# sensor.net
KiCad netlist of a schematic drawn in EAGLE
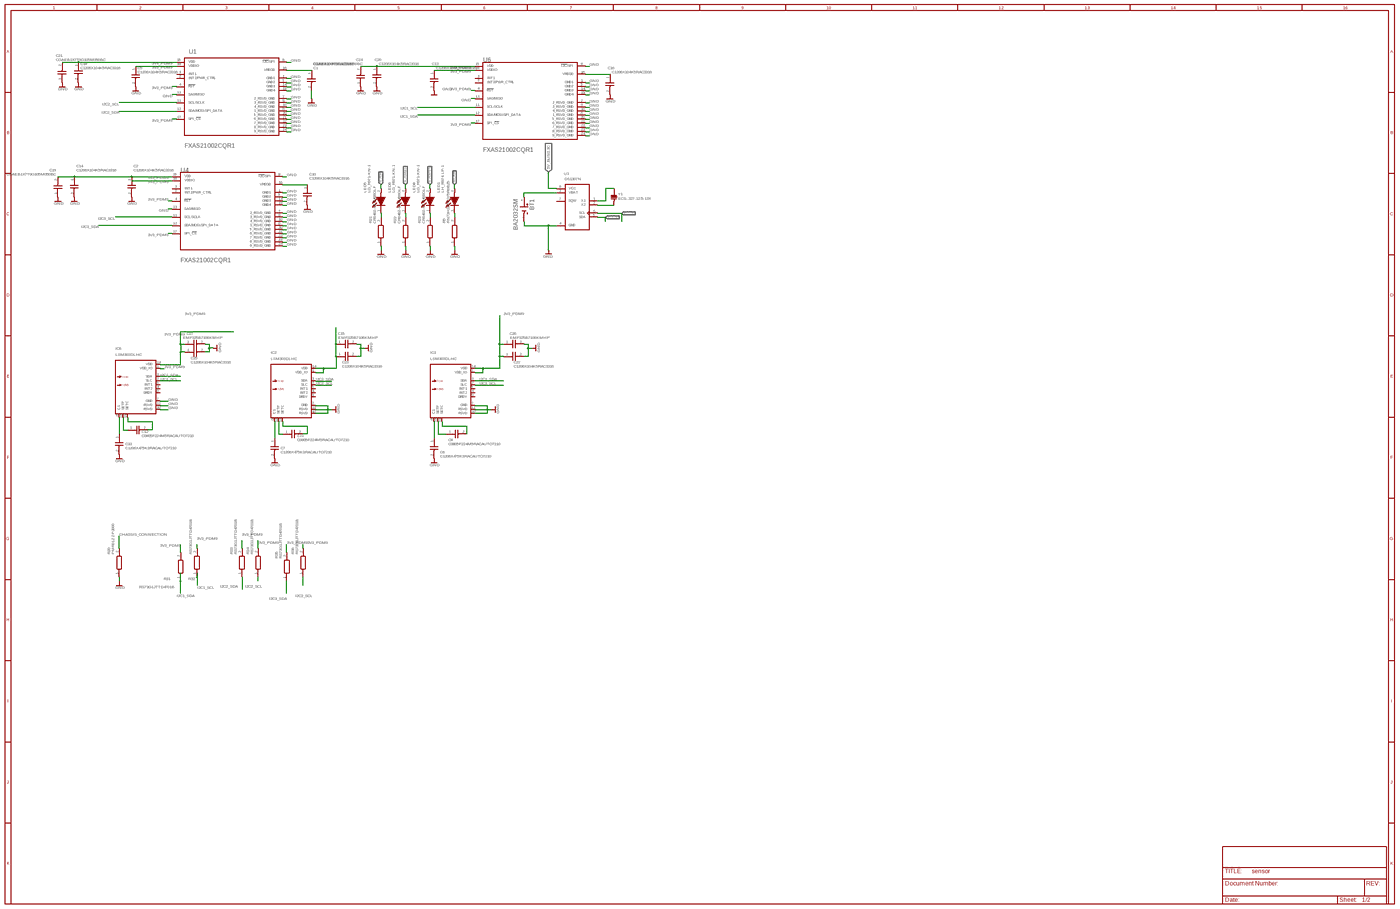
[diagram p0: schematic, sheet 1, overview]
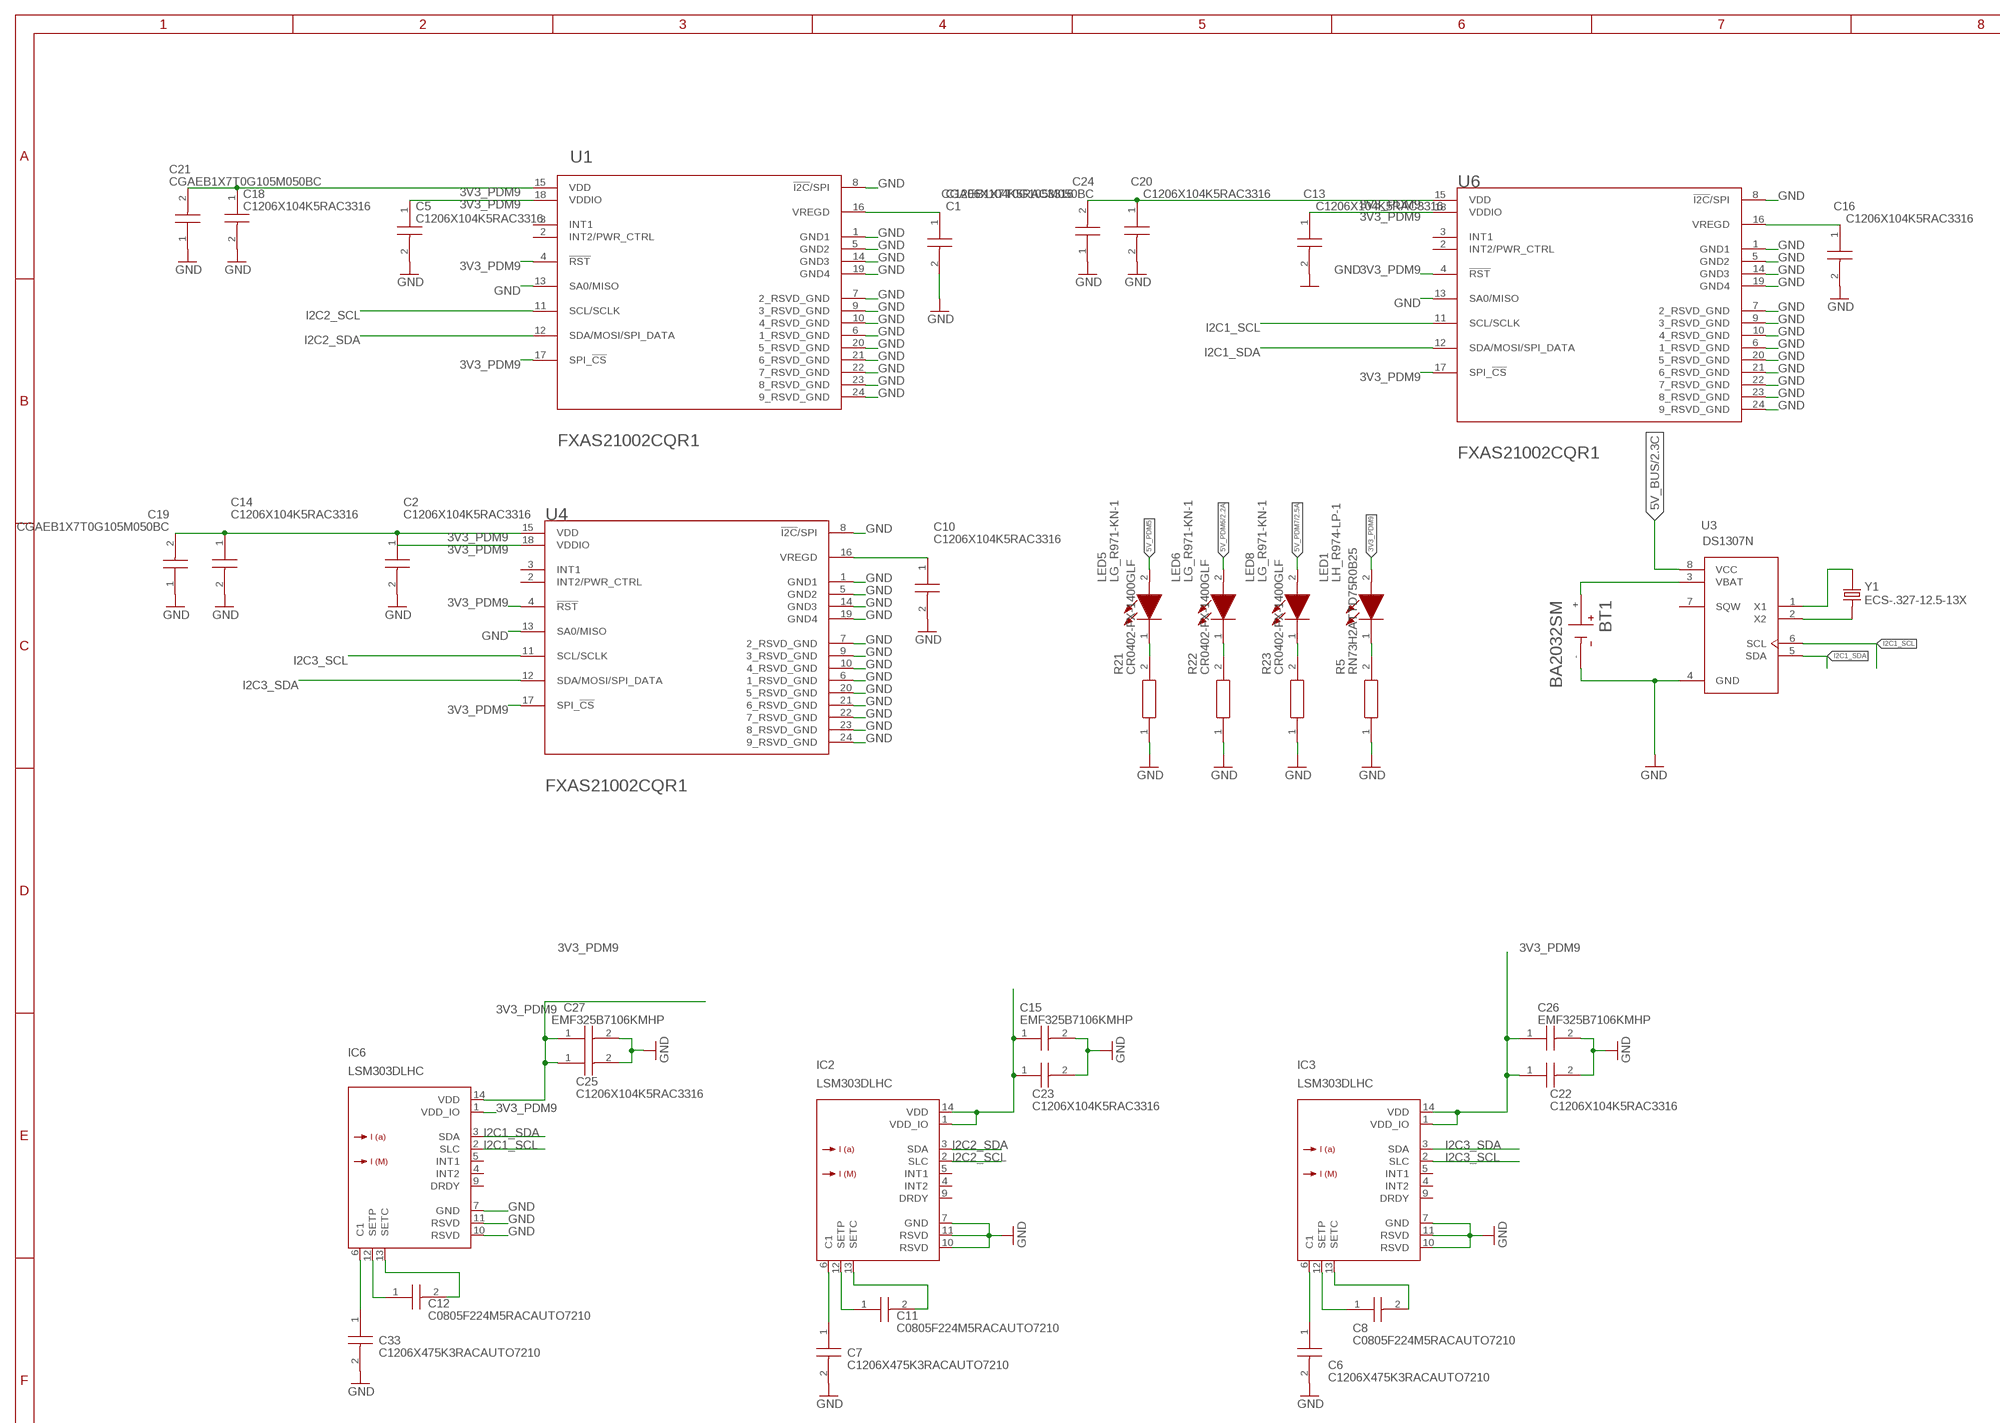
[diagram p1: schematic, sheet 1, part 1 of 4]
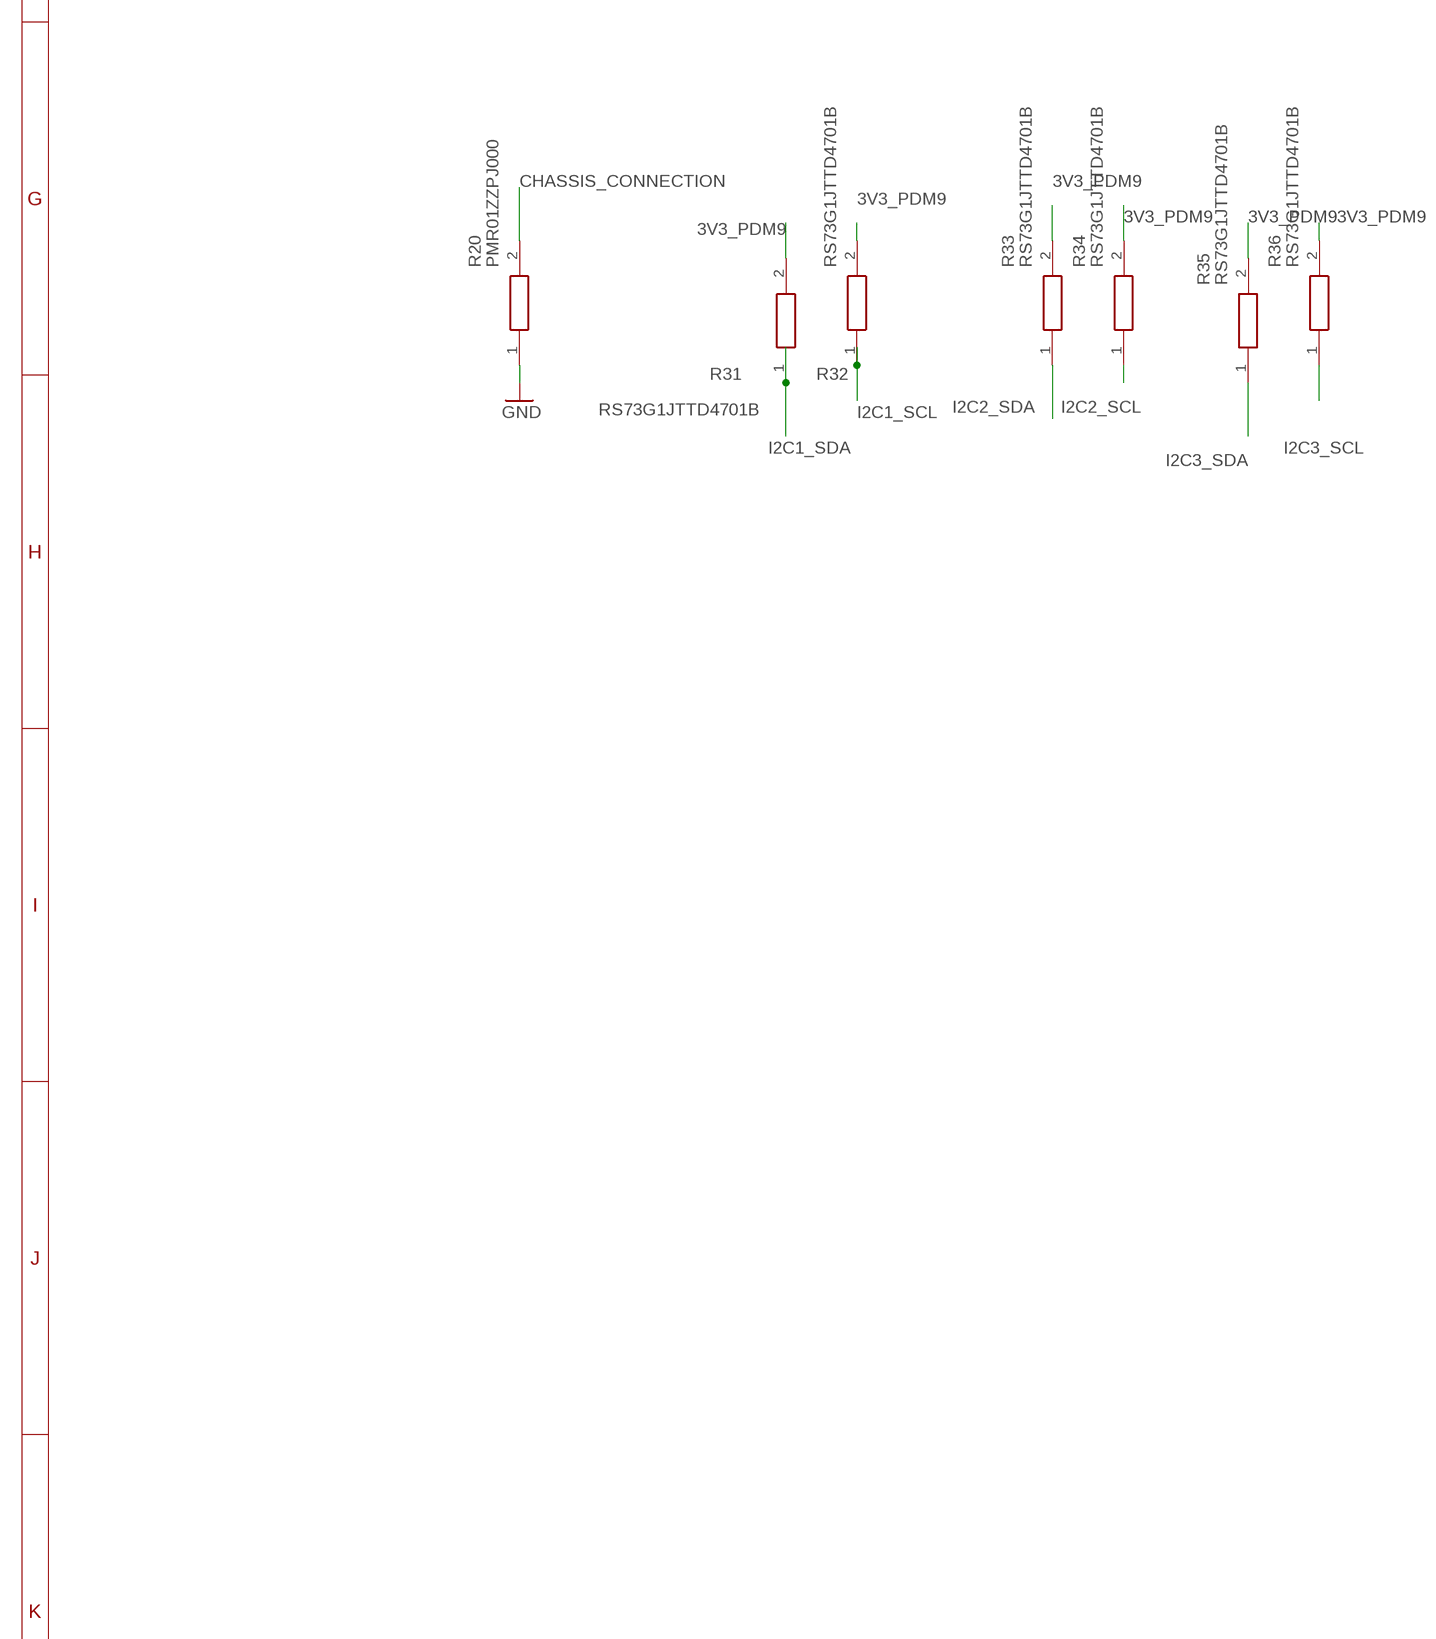
[diagram p2: schematic, sheet 1, part 2 of 4]
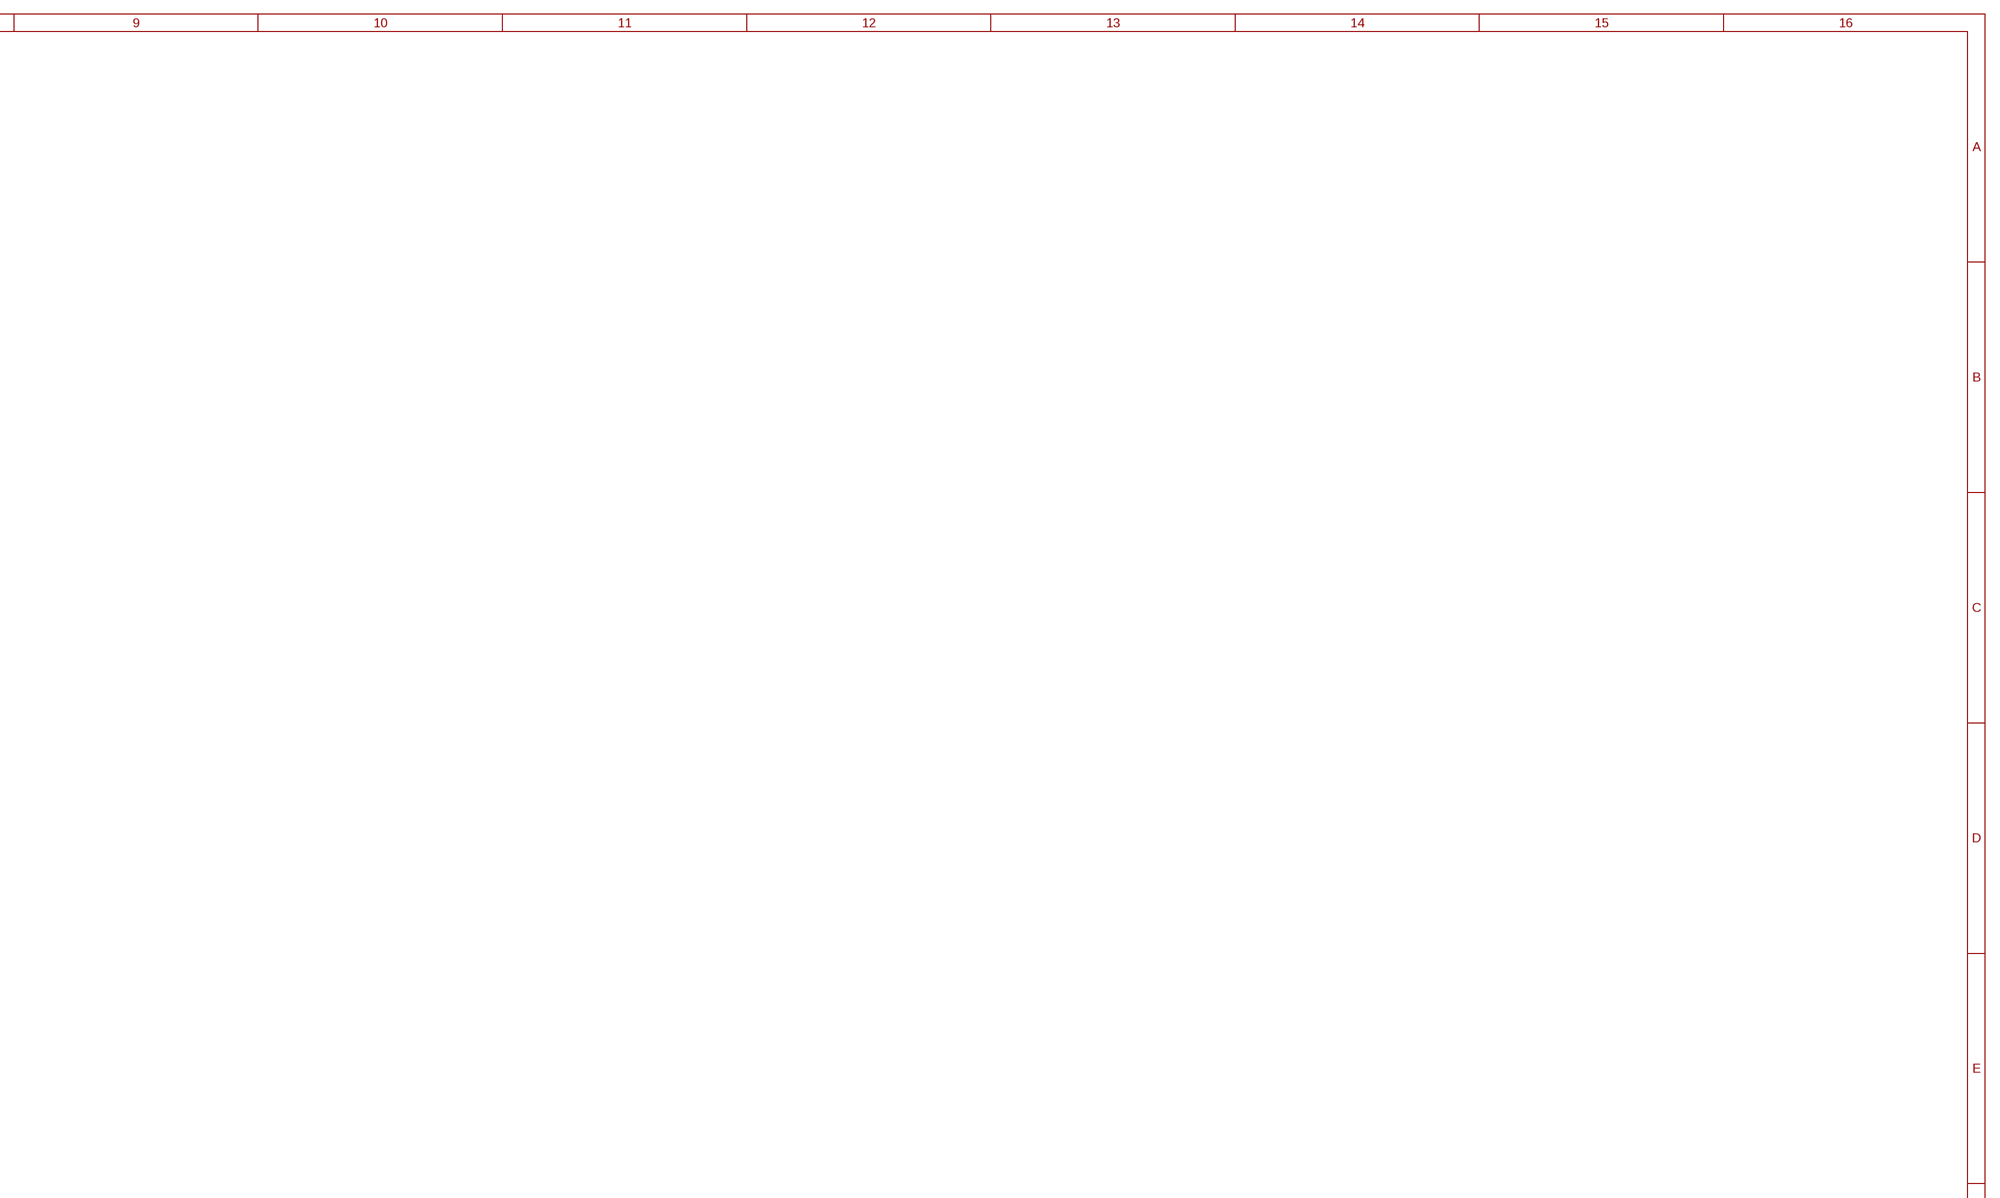
[diagram p3: schematic, sheet 1, part 3 of 4]
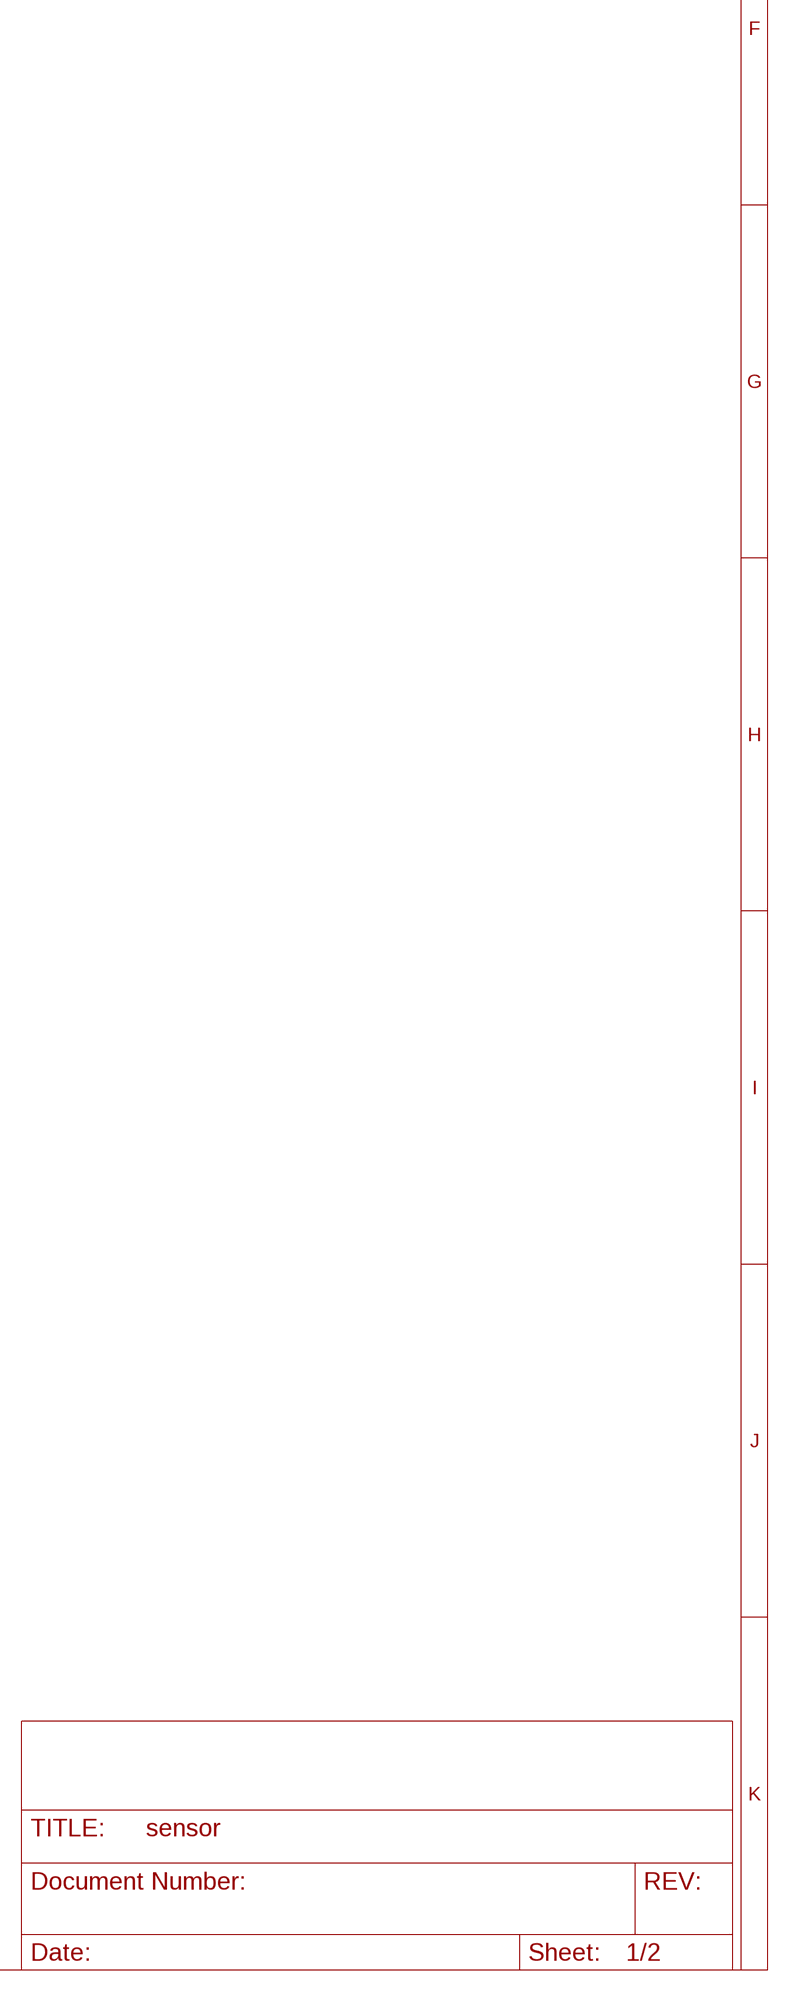
[diagram p4: schematic, sheet 1, part 4 of 4]
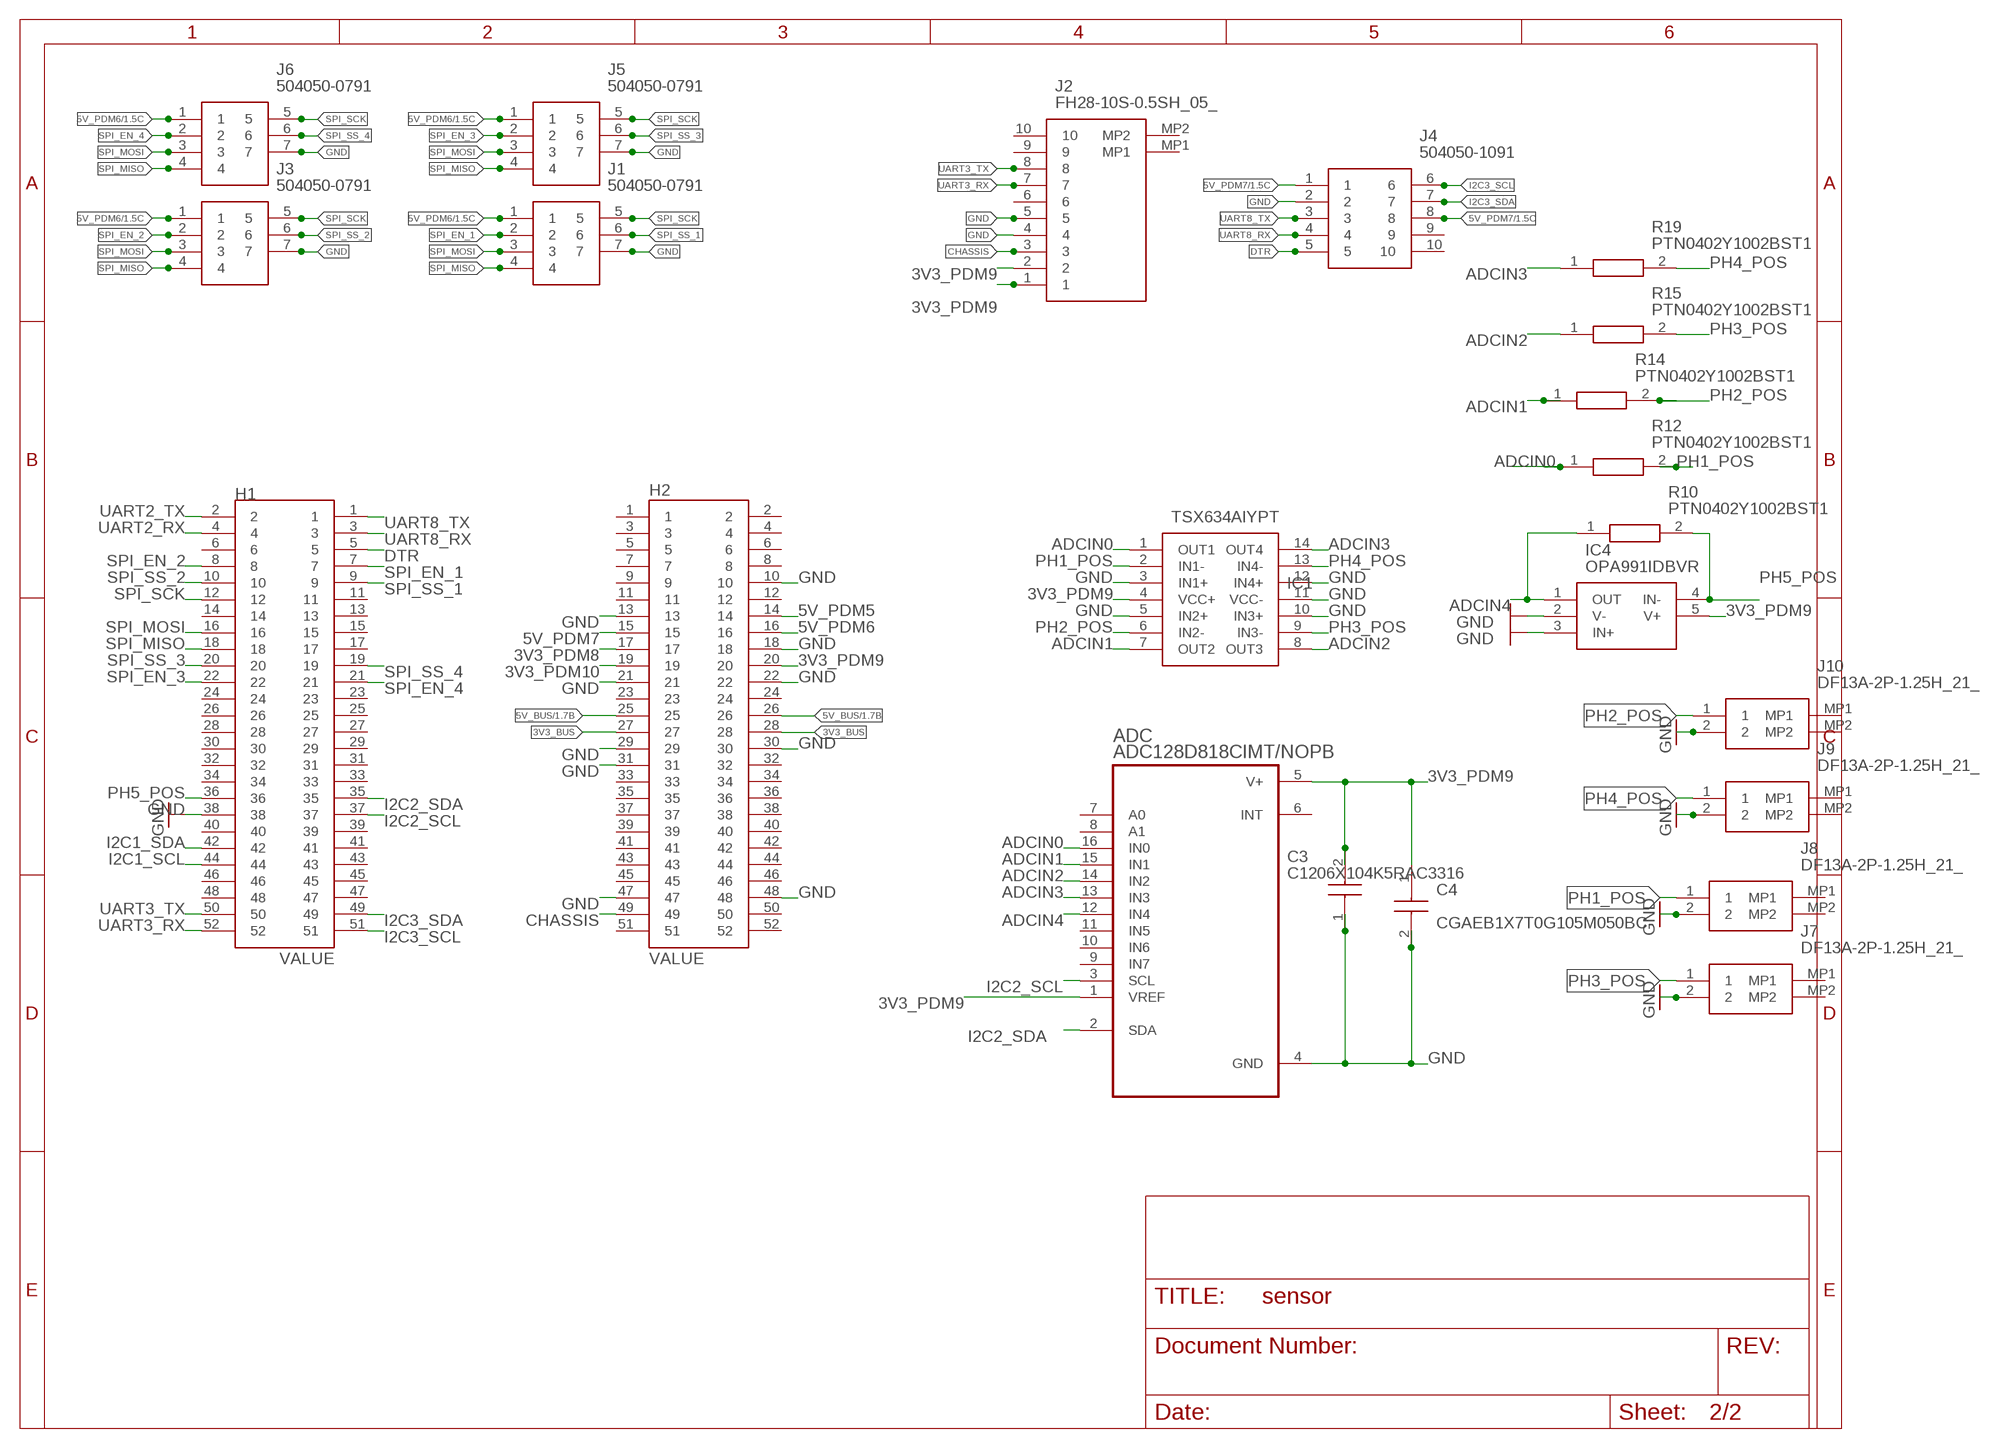
[diagram p5: schematic, sheet 2]

(export (version "E")
  (design (tool "Eeschema 10.0.6"))
  (components
    (comp (ref "BT1")
      (value "BA2032SM")
      (footprint "eagle-import:BAT_BA2032SM")
      (fields (field (name "DIGI-KEY_PART_NUMBER") "BA2032SM-ND") (field (name "MF") "MPD"))
      (libsource (lib "eagle-import") (part "BA2032SM"))
    )
    (comp (ref "C1")
      (value "C1206X104K5RAC3316")
      (footprint "eagle-import:CAPC3316X98N")
      (fields (field (name "MOUSER_PART_NUMBER") "80-C1206X104K5RC3316"))
      (libsource (lib "eagle-import") (part "C1206X104K5RAC3316"))
    )
    (comp (ref "C2")
      (value "C1206X104K5RAC3316")
      (footprint "eagle-import:CAPC3316X98N")
      (fields (field (name "MOUSER_PART_NUMBER") "80-C1206X104K5RC3316"))
      (libsource (lib "eagle-import") (part "C1206X104K5RAC3316"))
    )
    (comp (ref "C5")
      (value "C1206X104K5RAC3316")
      (footprint "eagle-import:CAPC3316X98N")
      (fields (field (name "MOUSER_PART_NUMBER") "80-C1206X104K5RC3316"))
      (libsource (lib "eagle-import") (part "C1206X104K5RAC3316"))
    )
    (comp (ref "C6")
      (value "C1206X475K3RACAUTO7210")
      (footprint "eagle-import:CAPC3316X195N")
      (fields (field (name "MOUSER_PART_NUMBER") "80-C1206X475K3RAUTLR"))
      (libsource (lib "eagle-import") (part "C1206X475K3RACAUTO7210"))
    )
    (comp (ref "C7")
      (value "C1206X475K3RACAUTO7210")
      (footprint "eagle-import:CAPC3316X195N")
      (fields (field (name "MOUSER_PART_NUMBER") "80-C1206X475K3RAUTLR"))
      (libsource (lib "eagle-import") (part "C1206X475K3RACAUTO7210"))
    )
    (comp (ref "C8")
      (value "C0805F224M5RACAUTO7210")
      (footprint "eagle-import:CAPC2012X140N")
      (fields (field (name "MOUSER_PART_NUMBER") "80-C0805F224M5RAUTLR"))
      (libsource (lib "eagle-import") (part "C0805F224M5RACAUTO7210"))
    )
    (comp (ref "C10")
      (value "C1206X104K5RAC3316")
      (footprint "eagle-import:CAPC3316X98N")
      (fields (field (name "MOUSER_PART_NUMBER") "80-C1206X104K5RC3316"))
      (libsource (lib "eagle-import") (part "C1206X104K5RAC3316"))
    )
    (comp (ref "C11")
      (value "C0805F224M5RACAUTO7210")
      (footprint "eagle-import:CAPC2012X140N")
      (fields (field (name "MOUSER_PART_NUMBER") "80-C0805F224M5RAUTLR"))
      (libsource (lib "eagle-import") (part "C0805F224M5RACAUTO7210"))
    )
    (comp (ref "C12")
      (value "C0805F224M5RACAUTO7210")
      (footprint "eagle-import:CAPC2012X140N")
      (fields (field (name "MOUSER_PART_NUMBER") "80-C0805F224M5RAUTLR"))
      (libsource (lib "eagle-import") (part "C0805F224M5RACAUTO7210"))
    )
    (comp (ref "C13")
      (value "C1206X104K5RAC3316")
      (footprint "eagle-import:CAPC3316X98N")
      (fields (field (name "MOUSER_PART_NUMBER") "80-C1206X104K5RC3316"))
      (libsource (lib "eagle-import") (part "C1206X104K5RAC3316"))
    )
    (comp (ref "C14")
      (value "C1206X104K5RAC3316")
      (footprint "eagle-import:CAPC3316X98N")
      (fields (field (name "MOUSER_PART_NUMBER") "80-C1206X104K5RC3316"))
      (libsource (lib "eagle-import") (part "C1206X104K5RAC3316"))
    )
    (comp (ref "C15")
      (value "EMF325B7106KMHP")
      (footprint "eagle-import:CAPC3225X270N")
      (fields (field (name "MOUSER_PART_NUMBER") "963-EMF325B7106KMHP"))
      (libsource (lib "eagle-import") (part "EMF325B7106KMHP"))
    )
    (comp (ref "C16")
      (value "C1206X104K5RAC3316")
      (footprint "eagle-import:CAPC3316X98N")
      (fields (field (name "MOUSER_PART_NUMBER") "80-C1206X104K5RC3316"))
      (libsource (lib "eagle-import") (part "C1206X104K5RAC3316"))
    )
    (comp (ref "C18")
      (value "C1206X104K5RAC3316")
      (footprint "eagle-import:CAPC3316X98N")
      (fields (field (name "MOUSER_PART_NUMBER") "80-C1206X104K5RC3316"))
      (libsource (lib "eagle-import") (part "C1206X104K5RAC3316"))
    )
    (comp (ref "C19")
      (value "CGAEB1X7T0G105M050BC")
      (footprint "eagle-import:CAPC0611X68N")
      (fields (field (name "MOUSER_PART_NUMBER") "810-CGAEB1X7T0G105M5"))
      (libsource (lib "eagle-import") (part "CGAEB1X7T0G105M050BC"))
    )
    (comp (ref "C20")
      (value "C1206X104K5RAC3316")
      (footprint "eagle-import:CAPC3316X98N")
      (fields (field (name "MOUSER_PART_NUMBER") "80-C1206X104K5RC3316"))
      (libsource (lib "eagle-import") (part "C1206X104K5RAC3316"))
    )
    (comp (ref "C21")
      (value "CGAEB1X7T0G105M050BC")
      (footprint "eagle-import:CAPC0611X68N")
      (fields (field (name "MOUSER_PART_NUMBER") "810-CGAEB1X7T0G105M5"))
      (libsource (lib "eagle-import") (part "CGAEB1X7T0G105M050BC"))
    )
    (comp (ref "C22")
      (value "C1206X104K5RAC3316")
      (footprint "eagle-import:CAPC3316X98N")
      (fields (field (name "MOUSER_PART_NUMBER") "80-C1206X104K5RC3316"))
      (libsource (lib "eagle-import") (part "C1206X104K5RAC3316"))
    )
    (comp (ref "C23")
      (value "C1206X104K5RAC3316")
      (footprint "eagle-import:CAPC3316X98N")
      (fields (field (name "MOUSER_PART_NUMBER") "80-C1206X104K5RC3316"))
      (libsource (lib "eagle-import") (part "C1206X104K5RAC3316"))
    )
    (comp (ref "C24")
      (value "CGAEB1X7T0G105M050BC")
      (footprint "eagle-import:CAPC0611X68N")
      (fields (field (name "MOUSER_PART_NUMBER") "810-CGAEB1X7T0G105M5"))
      (libsource (lib "eagle-import") (part "CGAEB1X7T0G105M050BC"))
    )
    (comp (ref "C25")
      (value "C1206X104K5RAC3316")
      (footprint "eagle-import:CAPC3316X98N")
      (fields (field (name "MOUSER_PART_NUMBER") "80-C1206X104K5RC3316"))
      (libsource (lib "eagle-import") (part "C1206X104K5RAC3316"))
    )
    (comp (ref "C26")
      (value "EMF325B7106KMHP")
      (footprint "eagle-import:CAPC3225X270N")
      (fields (field (name "MOUSER_PART_NUMBER") "963-EMF325B7106KMHP"))
      (libsource (lib "eagle-import") (part "EMF325B7106KMHP"))
    )
    (comp (ref "C27")
      (value "EMF325B7106KMHP")
      (footprint "eagle-import:CAPC3225X270N")
      (fields (field (name "MOUSER_PART_NUMBER") "963-EMF325B7106KMHP"))
      (libsource (lib "eagle-import") (part "EMF325B7106KMHP"))
    )
    (comp (ref "C33")
      (value "C1206X475K3RACAUTO7210")
      (footprint "eagle-import:CAPC3316X195N")
      (fields (field (name "MOUSER_PART_NUMBER") "80-C1206X475K3RAUTLR"))
      (libsource (lib "eagle-import") (part "C1206X475K3RACAUTO7210"))
    )
    (comp (ref "IC2")
      (value "LSM303DLHC")
      (footprint "eagle-import:LGA-14")
      (libsource (lib "eagle-import") (part "LSM303DLHC"))
    )
    (comp (ref "IC3")
      (value "LSM303DLHC")
      (footprint "eagle-import:LGA-14")
      (libsource (lib "eagle-import") (part "LSM303DLHC"))
    )
    (comp (ref "IC6")
      (value "LSM303DLHC")
      (footprint "eagle-import:LGA-14")
      (libsource (lib "eagle-import") (part "LSM303DLHC"))
    )
    (comp (ref "LED1")
      (value "LH_R974-LP-1")
      (footprint "eagle-import:LEDC2012X90N")
      (fields
        (field (name "MANUFACTURER_PART_NUMBER") "LH R974-LP-1")
        (field (name "MOUSER_PART_NUMBER") "720-LHR974-LP-1")
      )
      (libsource (lib "eagle-import") (part "LH_R974-LP-1"))
    )
    (comp (ref "LED5")
      (value "LG_R971-KN-1")
      (footprint "eagle-import:LEDC2012X80N")
      (fields
        (field (name "MANUFACTURER_PART_NUMBER") "LG R971-KN-1")
        (field (name "MOUSER_PART_NUMBER") "720-LGR971-KN-1")
      )
      (libsource (lib "eagle-import") (part "LG_R971-KN-1"))
    )
    (comp (ref "LED6")
      (value "LG_R971-KN-1")
      (footprint "eagle-import:LEDC2012X80N")
      (fields
        (field (name "MANUFACTURER_PART_NUMBER") "LG R971-KN-1")
        (field (name "MOUSER_PART_NUMBER") "720-LGR971-KN-1")
      )
      (libsource (lib "eagle-import") (part "LG_R971-KN-1"))
    )
    (comp (ref "LED8")
      (value "LG_R971-KN-1")
      (footprint "eagle-import:LEDC2012X80N")
      (fields
        (field (name "MANUFACTURER_PART_NUMBER") "LG R971-KN-1")
        (field (name "MOUSER_PART_NUMBER") "720-LGR971-KN-1")
      )
      (libsource (lib "eagle-import") (part "LG_R971-KN-1"))
    )
    (comp (ref "R5")
      (value "RN73H2ATTD75R0B25")
      (footprint "eagle-import:RESC2012X60N")
      (fields (field (name "MOUSER_PART_NUMBER") "660-RN73H2TD75R0B25"))
      (libsource (lib "eagle-import") (part "RN73H2ATTD75R0B25"))
    )
    (comp (ref "R20")
      (value "PMR01ZZPJ000")
      (footprint "eagle-import:RESC1005X35N")
      (fields (field (name "MOUSER_PART_NUMBER") "755-PMR01ZZPJ000"))
      (libsource (lib "eagle-import") (part "PMR01ZZPJ000"))
    )
    (comp (ref "R21")
      (value "CR0402-FX-1400GLF")
      (footprint "eagle-import:RESC1005X40N")
      (fields (field (name "MOUSER_PART_NUMBER") "652-CR0402FX1400GLF"))
      (libsource (lib "eagle-import") (part "CR0402-FX-1400GLF"))
    )
    (comp (ref "R22")
      (value "CR0402-FX-1400GLF")
      (footprint "eagle-import:RESC1005X40N")
      (fields (field (name "MOUSER_PART_NUMBER") "652-CR0402FX1400GLF"))
      (libsource (lib "eagle-import") (part "CR0402-FX-1400GLF"))
    )
    (comp (ref "R23")
      (value "CR0402-FX-1400GLF")
      (footprint "eagle-import:RESC1005X40N")
      (fields (field (name "MOUSER_PART_NUMBER") "652-CR0402FX1400GLF"))
      (libsource (lib "eagle-import") (part "CR0402-FX-1400GLF"))
    )
    (comp (ref "R31")
      (value "RS73G1JTTD4701B")
      (footprint "eagle-import:RESC1608X55N")
      (fields (field (name "MOUSER_PART_NUMBER") "660-RS73G1JTTD4701B"))
      (libsource (lib "eagle-import") (part "RS73G1JTTD4701B"))
    )
    (comp (ref "R32")
      (value "RS73G1JTTD4701B")
      (footprint "eagle-import:RESC1608X55N")
      (fields (field (name "MOUSER_PART_NUMBER") "660-RS73G1JTTD4701B"))
      (libsource (lib "eagle-import") (part "RS73G1JTTD4701B"))
    )
    (comp (ref "R33")
      (value "RS73G1JTTD4701B")
      (footprint "eagle-import:RESC1608X55N")
      (fields (field (name "MOUSER_PART_NUMBER") "660-RS73G1JTTD4701B"))
      (libsource (lib "eagle-import") (part "RS73G1JTTD4701B"))
    )
    (comp (ref "R34")
      (value "RS73G1JTTD4701B")
      (footprint "eagle-import:RESC1608X55N")
      (fields (field (name "MOUSER_PART_NUMBER") "660-RS73G1JTTD4701B"))
      (libsource (lib "eagle-import") (part "RS73G1JTTD4701B"))
    )
    (comp (ref "R35")
      (value "RS73G1JTTD4701B")
      (footprint "eagle-import:RESC1608X55N")
      (fields (field (name "MOUSER_PART_NUMBER") "660-RS73G1JTTD4701B"))
      (libsource (lib "eagle-import") (part "RS73G1JTTD4701B"))
    )
    (comp (ref "R36")
      (value "RS73G1JTTD4701B")
      (footprint "eagle-import:RESC1608X55N")
      (fields (field (name "MOUSER_PART_NUMBER") "660-RS73G1JTTD4701B"))
      (libsource (lib "eagle-import") (part "RS73G1JTTD4701B"))
    )
    (comp (ref "U1")
      (value "NXP_FXAS21002CQR1_EDITEDNXP_FXAS21002CQR1_0_0")
      (footprint "eagle-import:NXP_FXAS21002CQR1_0_EDITED")
      (fields
        (field (name "DIGIKEY_PART_NUMBER") "FXAS21002CQR1CT-ND")
        (field (name "MF") "NXP")
        (field (name "MOUSER_PART_NUMBER") "841-FXAS21002CQR1")
      )
      (libsource (lib "eagle-import") (part "NXP_FXAS21002CQR1_EDITEDNXP_FXAS21002CQR1_0_0"))
    )
    (comp (ref "U3")
      (value "DS1307N")
      (footprint "eagle-import:DIP762W47P254L991H457Q8")
      (fields
        (field (name "DIGI-KEY_PART_NUMBER") "DS1307N+-ND")
        (field (name "MF") "Maxim Integrated")
        (field (name "MP") "DS1307N+")
      )
      (libsource (lib "eagle-import") (part "DS1307N"))
    )
    (comp (ref "U4")
      (value "NXP_FXAS21002CQR1_EDITEDNXP_FXAS21002CQR1_0_0")
      (footprint "eagle-import:NXP_FXAS21002CQR1_0_EDITED")
      (fields
        (field (name "DIGIKEY_PART_NUMBER") "FXAS21002CQR1CT-ND")
        (field (name "MF") "NXP")
        (field (name "MOUSER_PART_NUMBER") "841-FXAS21002CQR1")
      )
      (libsource (lib "eagle-import") (part "NXP_FXAS21002CQR1_EDITEDNXP_FXAS21002CQR1_0_0"))
    )
    (comp (ref "U6")
      (value "NXP_FXAS21002CQR1_EDITEDNXP_FXAS21002CQR1_0_0")
      (footprint "eagle-import:NXP_FXAS21002CQR1_0_EDITED")
      (fields
        (field (name "DIGIKEY_PART_NUMBER") "FXAS21002CQR1CT-ND")
        (field (name "MF") "NXP")
        (field (name "MOUSER_PART_NUMBER") "841-FXAS21002CQR1")
      )
      (libsource (lib "eagle-import") (part "NXP_FXAS21002CQR1_EDITEDNXP_FXAS21002CQR1_0_0"))
    )
    (comp (ref "Y1")
      (value "ECS-.327-12.5-13X")
      (footprint "eagle-import:XTAL_ECS-.327-12.5-13X")
      (fields (field (name "DIGI-KEY_PART_NUMBER") "X1124-ND") (field (name "MF") "ECS Inc."))
      (libsource (lib "eagle-import") (part "ECS-.327-12.5-13X"))
    )
    (comp (ref "ADC")
      (value "ADC128D818CIMT/NOPB")
      (footprint "eagle-import:SOP65P640X120-16N")
      (fields
        (field (name "DIGI-KEY_PART_NUMBER") "ADC128D818CIMT/NOPB-ND")
        (field (name "MF") "Texas Instruments")
      )
      (libsource (lib "eagle-import") (part "ADC128D818CIMT/NOPB"))
    )
    (comp (ref "C3")
      (value "C1206X104K5RAC3316")
      (footprint "eagle-import:CAPC3316X98N")
      (fields (field (name "MOUSER_PART_NUMBER") "80-C1206X104K5RC3316"))
      (libsource (lib "eagle-import") (part "C1206X104K5RAC3316"))
    )
    (comp (ref "C4")
      (value "CGAEB1X7T0G105M050BC")
      (footprint "eagle-import:CAPC0611X68N")
      (fields (field (name "MOUSER_PART_NUMBER") "810-CGAEB1X7T0G105M5"))
      (libsource (lib "eagle-import") (part "CGAEB1X7T0G105M050BC"))
    )
    (comp (ref "H1")
      (value "ESQ-126-39-G-D")
      (footprint "eagle-import:SAMTEC_ESQ-126-39-G-D")
      (fields (field (name "DIGI-KEY_PART_NUMBER") "SAM10462-ND") (field (name "MF") "Samtec"))
      (libsource (lib "eagle-import") (part "ESQ-126-39-G-D"))
    )
    (comp (ref "H2")
      (value "ESQ-126-39-G-D")
      (footprint "eagle-import:SAMTEC_ESQ-126-39-G-D")
      (fields (field (name "DIGI-KEY_PART_NUMBER") "SAM10462-ND") (field (name "MF") "Samtec"))
      (libsource (lib "eagle-import") (part "ESQ-126-39-G-D"))
    )
    (comp (ref "IC1")
      (value "TSX634AIYPT")
      (footprint "eagle-import:SOP65P640X120-14N")
      (fields (field (name "MOUSER_PART_NUMBER") "511-TSX634AIYPT"))
      (libsource (lib "eagle-import") (part "TSX634AIYPT"))
    )
    (comp (ref "IC4")
      (value "OPA991IDBVR")
      (footprint "eagle-import:SOT95P280X145-5N")
      (fields (field (name "MOUSER_PART_NUMBER") "595-OPA991IDBVR"))
      (libsource (lib "eagle-import") (part "OPA991IDBVR"))
    )
    (comp (ref "J1")
      (value "504050-0791")
      (footprint "eagle-import:504050-0791")
      (fields (field (name "MOUSER_PART_NUMBER") "538-504050-0791"))
      (libsource (lib "eagle-import") (part "504050-0791"))
    )
    (comp (ref "J2")
      (value "FH28-10S-0.5SH_05_")
      (footprint "eagle-import:FH2810S05SH05")
      (fields
        (field (name "MANUFACTURER_PART_NUMBER") "FH28-10S-0.5SH(05)")
        (field (name "MOUSER_PART_NUMBER") "798-FH2810S05SH05")
      )
      (libsource (lib "eagle-import") (part "FH28-10S-0.5SH_05_"))
    )
    (comp (ref "J3")
      (value "504050-0791")
      (footprint "eagle-import:504050-0791")
      (fields (field (name "MOUSER_PART_NUMBER") "538-504050-0791"))
      (libsource (lib "eagle-import") (part "504050-0791"))
    )
    (comp (ref "J4")
      (value "504050-1091")
      (footprint "eagle-import:504050-1091")
      (fields (field (name "MOUSER_PART_NUMBER") "538-504050-1091"))
      (libsource (lib "eagle-import") (part "504050-1091"))
    )
    (comp (ref "J5")
      (value "504050-0791")
      (footprint "eagle-import:504050-0791")
      (fields (field (name "MOUSER_PART_NUMBER") "538-504050-0791"))
      (libsource (lib "eagle-import") (part "504050-0791"))
    )
    (comp (ref "J6")
      (value "504050-0791")
      (footprint "eagle-import:504050-0791")
      (fields (field (name "MOUSER_PART_NUMBER") "538-504050-0791"))
      (libsource (lib "eagle-import") (part "504050-0791"))
    )
    (comp (ref "J7")
      (value "DF13A-2P-1.25H_21_")
      (footprint "eagle-import:DF13A2P125H21")
      (fields
        (field (name "MANUFACTURER_PART_NUMBER") "DF13A-2P-1.25H(21)")
        (field (name "MOUSER_PART_NUMBER") "798-DF13A2P125H21")
      )
      (libsource (lib "eagle-import") (part "DF13A-2P-1.25H_21_"))
    )
    (comp (ref "J8")
      (value "DF13A-2P-1.25H_21_")
      (footprint "eagle-import:DF13A2P125H21")
      (fields
        (field (name "MANUFACTURER_PART_NUMBER") "DF13A-2P-1.25H(21)")
        (field (name "MOUSER_PART_NUMBER") "798-DF13A2P125H21")
      )
      (libsource (lib "eagle-import") (part "DF13A-2P-1.25H_21_"))
    )
    (comp (ref "J9")
      (value "DF13A-2P-1.25H_21_")
      (footprint "eagle-import:DF13A2P125H21")
      (fields
        (field (name "MANUFACTURER_PART_NUMBER") "DF13A-2P-1.25H(21)")
        (field (name "MOUSER_PART_NUMBER") "798-DF13A2P125H21")
      )
      (libsource (lib "eagle-import") (part "DF13A-2P-1.25H_21_"))
    )
    (comp (ref "J10")
      (value "DF13A-2P-1.25H_21_")
      (footprint "eagle-import:DF13A2P125H21")
      (fields
        (field (name "MANUFACTURER_PART_NUMBER") "DF13A-2P-1.25H(21)")
        (field (name "MOUSER_PART_NUMBER") "798-DF13A2P125H21")
      )
      (libsource (lib "eagle-import") (part "DF13A-2P-1.25H_21_"))
    )
    (comp (ref "R10")
      (value "PTN0402Y1002BST1")
      (footprint "eagle-import:RESC1106X84N")
      (fields (field (name "MOUSER_PART_NUMBER") "71-PTN0402Y1002BST1"))
      (libsource (lib "eagle-import") (part "PTN0402Y1002BST1"))
    )
    (comp (ref "R12")
      (value "PTN0402Y1002BST1")
      (footprint "eagle-import:RESC1106X84N")
      (fields (field (name "MOUSER_PART_NUMBER") "71-PTN0402Y1002BST1"))
      (libsource (lib "eagle-import") (part "PTN0402Y1002BST1"))
    )
    (comp (ref "R14")
      (value "PTN0402Y1002BST1")
      (footprint "eagle-import:RESC1106X84N")
      (fields (field (name "MOUSER_PART_NUMBER") "71-PTN0402Y1002BST1"))
      (libsource (lib "eagle-import") (part "PTN0402Y1002BST1"))
    )
    (comp (ref "R15")
      (value "PTN0402Y1002BST1")
      (footprint "eagle-import:RESC1106X84N")
      (fields (field (name "MOUSER_PART_NUMBER") "71-PTN0402Y1002BST1"))
      (libsource (lib "eagle-import") (part "PTN0402Y1002BST1"))
    )
    (comp (ref "R19")
      (value "PTN0402Y1002BST1")
      (footprint "eagle-import:RESC1106X84N")
      (fields (field (name "MOUSER_PART_NUMBER") "71-PTN0402Y1002BST1"))
      (libsource (lib "eagle-import") (part "PTN0402Y1002BST1"))
    )
  )
  (nets
    (net (code "1") (name "3V3_BUS") (class "Default")
      (node (ref "H2") (pin "27") (pinfunction "27_27") (pintype "passive"))
      (node (ref "H2") (pin "28") (pinfunction "28_28") (pintype "passive"))
    )
    (net (code "2") (name "3V3_PDM8") (class "Default")
      (node (ref "H2") (pin "17") (pinfunction "17_17") (pintype "passive"))
    )
    (net (code "3") (name "3V3_PDM9") (class "Default")
      (node (ref "ADC") (pin "1") (pinfunction "VREF_1") (pintype "input"))
      (node (ref "ADC") (pin "5") (pinfunction "V+_5") (pintype "power_in"))
      (node (ref "C13") (pin "1") (pinfunction "1_1") (pintype "bidirectional"))
      (node (ref "C14") (pin "1") (pinfunction "1_1") (pintype "bidirectional"))
      (node (ref "C15") (pin "1") (pinfunction "1_1") (pintype "bidirectional"))
      (node (ref "C18") (pin "1") (pinfunction "1_1") (pintype "bidirectional"))
      (node (ref "C19") (pin "2") (pinfunction "2_2") (pintype "bidirectional"))
      (node (ref "C2") (pin "1") (pinfunction "1_1") (pintype "bidirectional"))
      (node (ref "C20") (pin "1") (pinfunction "1_1") (pintype "bidirectional"))
      (node (ref "C21") (pin "2") (pinfunction "2_2") (pintype "bidirectional"))
      (node (ref "C22") (pin "1") (pinfunction "1_1") (pintype "bidirectional"))
      (node (ref "C23") (pin "1") (pinfunction "1_1") (pintype "bidirectional"))
      (node (ref "C24") (pin "2") (pinfunction "2_2") (pintype "bidirectional"))
      (node (ref "C25") (pin "1") (pinfunction "1_1") (pintype "bidirectional"))
      (node (ref "C26") (pin "1") (pinfunction "1_1") (pintype "bidirectional"))
      (node (ref "C27") (pin "1") (pinfunction "1_1") (pintype "bidirectional"))
      (node (ref "C3") (pin "2") (pinfunction "2_2") (pintype "bidirectional"))
      (node (ref "C4") (pin "1") (pinfunction "1_1") (pintype "bidirectional"))
      (node (ref "C5") (pin "1") (pinfunction "1_1") (pintype "bidirectional"))
      (node (ref "H2") (pin "20") (pinfunction "20_20") (pintype "passive"))
      (node (ref "IC1") (pin "4") (pinfunction "VCC+_4") (pintype "bidirectional"))
      (node (ref "IC2") (pin "1") (pinfunction "VDD_IO_1") (pintype "power_in"))
      (node (ref "IC2") (pin "14") (pinfunction "VDD_14") (pintype "power_in"))
      (node (ref "IC3") (pin "1") (pinfunction "VDD_IO_1") (pintype "power_in"))
      (node (ref "IC3") (pin "14") (pinfunction "VDD_14") (pintype "power_in"))
      (node (ref "IC4") (pin "5") (pinfunction "V+_5") (pintype "bidirectional"))
      (node (ref "IC6") (pin "1") (pinfunction "VDD_IO_1") (pintype "power_in"))
      (node (ref "IC6") (pin "14") (pinfunction "VDD_14") (pintype "power_in"))
      (node (ref "J2") (pin "1") (pinfunction "1_1") (pintype "bidirectional"))
      (node (ref "J2") (pin "2") (pinfunction "2_2") (pintype "bidirectional"))
      (node (ref "LED1") (pin "2") (pinfunction "A_2") (pintype "bidirectional"))
      (node (ref "R31") (pin "2") (pinfunction "2_2") (pintype "bidirectional"))
      (node (ref "R32") (pin "2") (pinfunction "2_2") (pintype "bidirectional"))
      (node (ref "R33") (pin "2") (pinfunction "2_2") (pintype "bidirectional"))
      (node (ref "R34") (pin "2") (pinfunction "2_2") (pintype "bidirectional"))
      (node (ref "R35") (pin "2") (pinfunction "2_2") (pintype "bidirectional"))
      (node (ref "R36") (pin "2") (pinfunction "2_2") (pintype "bidirectional"))
      (node (ref "U1") (pin "15") (pinfunction "VDD_15") (pintype "power_in"))
      (node (ref "U1") (pin "17") (pinfunction "SPI_~{CS}_17") (pintype "bidirectional"))
      (node (ref "U1") (pin "18") (pinfunction "VDDIO_18") (pintype "power_in"))
      (node (ref "U1") (pin "4") (pinfunction "~{RST}_4") (pintype "output"))
      (node (ref "U4") (pin "15") (pinfunction "VDD_15") (pintype "power_in"))
      (node (ref "U4") (pin "17") (pinfunction "SPI_~{CS}_17") (pintype "bidirectional"))
      (node (ref "U4") (pin "18") (pinfunction "VDDIO_18") (pintype "power_in"))
      (node (ref "U4") (pin "4") (pinfunction "~{RST}_4") (pintype "output"))
      (node (ref "U6") (pin "15") (pinfunction "VDD_15") (pintype "power_in"))
      (node (ref "U6") (pin "17") (pinfunction "SPI_~{CS}_17") (pintype "bidirectional"))
      (node (ref "U6") (pin "18") (pinfunction "VDDIO_18") (pintype "power_in"))
      (node (ref "U6") (pin "4") (pinfunction "~{RST}_4") (pintype "output"))
    )
    (net (code "4") (name "3V3_PDM10") (class "Default")
      (node (ref "H2") (pin "19") (pinfunction "19_19") (pintype "passive"))
    )
    (net (code "5") (name "5V_BUS") (class "Default")
      (node (ref "H2") (pin "25") (pinfunction "25_25") (pintype "passive"))
      (node (ref "H2") (pin "26") (pinfunction "26_26") (pintype "passive"))
      (node (ref "U3") (pin "8") (pinfunction "VCC_8") (pintype "power_in"))
    )
    (net (code "6") (name "5V_PDM5") (class "Default")
      (node (ref "H2") (pin "14") (pinfunction "14_14") (pintype "passive"))
      (node (ref "LED5") (pin "2") (pinfunction "A_2") (pintype "bidirectional"))
    )
    (net (code "7") (name "5V_PDM6") (class "Default")
      (node (ref "H2") (pin "16") (pinfunction "16_16") (pintype "passive"))
      (node (ref "J1") (pin "1") (pinfunction "1_1") (pintype "bidirectional"))
      (node (ref "J3") (pin "1") (pinfunction "1_1") (pintype "bidirectional"))
      (node (ref "J5") (pin "1") (pinfunction "1_1") (pintype "bidirectional"))
      (node (ref "J6") (pin "1") (pinfunction "1_1") (pintype "bidirectional"))
      (node (ref "LED6") (pin "2") (pinfunction "A_2") (pintype "bidirectional"))
    )
    (net (code "8") (name "5V_PDM7") (class "Default")
      (node (ref "H2") (pin "15") (pinfunction "15_15") (pintype "passive"))
      (node (ref "J4") (pin "1") (pinfunction "1_1") (pintype "bidirectional"))
      (node (ref "J4") (pin "8") (pinfunction "8_8") (pintype "bidirectional"))
      (node (ref "LED8") (pin "2") (pinfunction "A_2") (pintype "bidirectional"))
    )
    (net (code "9") (name "ADCIN0") (class "Default")
      (node (ref "ADC") (pin "16") (pinfunction "IN0_16") (pintype "input"))
      (node (ref "IC1") (pin "1") (pinfunction "OUT1_1") (pintype "bidirectional"))
      (node (ref "R12") (pin "1") (pinfunction "1_1") (pintype "bidirectional"))
    )
    (net (code "10") (name "ADCIN1") (class "Default")
      (node (ref "ADC") (pin "15") (pinfunction "IN1_15") (pintype "input"))
      (node (ref "IC1") (pin "7") (pinfunction "OUT2_7") (pintype "bidirectional"))
      (node (ref "R14") (pin "1") (pinfunction "1_1") (pintype "bidirectional"))
    )
    (net (code "11") (name "ADCIN2") (class "Default")
      (node (ref "ADC") (pin "14") (pinfunction "IN2_14") (pintype "input"))
      (node (ref "IC1") (pin "8") (pinfunction "OUT3_8") (pintype "bidirectional"))
      (node (ref "R15") (pin "1") (pinfunction "1_1") (pintype "bidirectional"))
    )
    (net (code "12") (name "ADCIN3") (class "Default")
      (node (ref "ADC") (pin "13") (pinfunction "IN3_13") (pintype "input"))
      (node (ref "IC1") (pin "14") (pinfunction "OUT4_14") (pintype "bidirectional"))
      (node (ref "R19") (pin "1") (pinfunction "1_1") (pintype "bidirectional"))
    )
    (net (code "13") (name "ADCIN4") (class "Default")
      (node (ref "ADC") (pin "12") (pinfunction "IN4_12") (pintype "input"))
      (node (ref "IC4") (pin "1") (pinfunction "OUT_1") (pintype "bidirectional"))
      (node (ref "R10") (pin "1") (pinfunction "1_1") (pintype "bidirectional"))
    )
    (net (code "14") (name "CHASSIS") (class "Default")
      (node (ref "H2") (pin "49") (pinfunction "49_49") (pintype "passive"))
      (node (ref "J2") (pin "3") (pinfunction "3_3") (pintype "bidirectional"))
    )
    (net (code "15") (name "CHASSIS_CONNECTION") (class "Default")
      (node (ref "R20") (pin "2") (pinfunction "2_2") (pintype "bidirectional"))
    )
    (net (code "16") (name "DTR") (class "Default")
      (node (ref "H1") (pin "5") (pinfunction "5_5") (pintype "passive"))
      (node (ref "J4") (pin "5") (pinfunction "5_5") (pintype "bidirectional"))
    )
    (net (code "17") (name "GND") (class "Default")
      (node (ref "ADC") (pin "4") (pinfunction "GND_4") (pintype "power_in"))
      (node (ref "BT1") (pin "-") (pinfunction "-_-") (pintype "passive"))
      (node (ref "C1") (pin "2") (pinfunction "2_2") (pintype "bidirectional"))
      (node (ref "C10") (pin "2") (pinfunction "2_2") (pintype "bidirectional"))
      (node (ref "C13") (pin "2") (pinfunction "2_2") (pintype "bidirectional"))
      (node (ref "C14") (pin "2") (pinfunction "2_2") (pintype "bidirectional"))
      (node (ref "C15") (pin "2") (pinfunction "2_2") (pintype "bidirectional"))
      (node (ref "C16") (pin "2") (pinfunction "2_2") (pintype "bidirectional"))
      (node (ref "C18") (pin "2") (pinfunction "2_2") (pintype "bidirectional"))
      (node (ref "C19") (pin "1") (pinfunction "1_1") (pintype "bidirectional"))
      (node (ref "C2") (pin "2") (pinfunction "2_2") (pintype "bidirectional"))
      (node (ref "C20") (pin "2") (pinfunction "2_2") (pintype "bidirectional"))
      (node (ref "C21") (pin "1") (pinfunction "1_1") (pintype "bidirectional"))
      (node (ref "C22") (pin "2") (pinfunction "2_2") (pintype "bidirectional"))
      (node (ref "C23") (pin "2") (pinfunction "2_2") (pintype "bidirectional"))
      (node (ref "C24") (pin "1") (pinfunction "1_1") (pintype "bidirectional"))
      (node (ref "C25") (pin "2") (pinfunction "2_2") (pintype "bidirectional"))
      (node (ref "C26") (pin "2") (pinfunction "2_2") (pintype "bidirectional"))
      (node (ref "C27") (pin "2") (pinfunction "2_2") (pintype "bidirectional"))
      (node (ref "C3") (pin "1") (pinfunction "1_1") (pintype "bidirectional"))
      (node (ref "C33") (pin "2") (pinfunction "2_2") (pintype "bidirectional"))
      (node (ref "C4") (pin "2") (pinfunction "2_2") (pintype "bidirectional"))
      (node (ref "C5") (pin "2") (pinfunction "2_2") (pintype "bidirectional"))
      (node (ref "C6") (pin "2") (pinfunction "2_2") (pintype "bidirectional"))
      (node (ref "C7") (pin "2") (pinfunction "2_2") (pintype "bidirectional"))
      (node (ref "H1") (pin "38") (pinfunction "38_38") (pintype "passive"))
      (node (ref "H2") (pin "10") (pinfunction "10_10") (pintype "passive"))
      (node (ref "H2") (pin "13") (pinfunction "13_13") (pintype "passive"))
      (node (ref "H2") (pin "18") (pinfunction "18_18") (pintype "passive"))
      (node (ref "H2") (pin "21") (pinfunction "21_21") (pintype "passive"))
      (node (ref "H2") (pin "22") (pinfunction "22_22") (pintype "passive"))
      (node (ref "H2") (pin "29") (pinfunction "29_29") (pintype "passive"))
      (node (ref "H2") (pin "30") (pinfunction "30_30") (pintype "passive"))
      (node (ref "H2") (pin "31") (pinfunction "31_31") (pintype "passive"))
      (node (ref "H2") (pin "47") (pinfunction "47_47") (pintype "passive"))
      (node (ref "H2") (pin "48") (pinfunction "48_48") (pintype "passive"))
      (node (ref "IC1") (pin "10") (pinfunction "IN3+_10") (pintype "bidirectional"))
      (node (ref "IC1") (pin "11") (pinfunction "VCC-_11") (pintype "bidirectional"))
      (node (ref "IC1") (pin "12") (pinfunction "IN4+_12") (pintype "bidirectional"))
      (node (ref "IC1") (pin "3") (pinfunction "IN1+_3") (pintype "bidirectional"))
      (node (ref "IC1") (pin "5") (pinfunction "IN2+_5") (pintype "bidirectional"))
      (node (ref "IC2") (pin "10") (pinfunction "RSVD_10") (pintype "passive"))
      (node (ref "IC2") (pin "11") (pinfunction "RSVD_11") (pintype "passive"))
      (node (ref "IC2") (pin "7") (pinfunction "GND_7") (pintype "power_in"))
      (node (ref "IC3") (pin "10") (pinfunction "RSVD_10") (pintype "passive"))
      (node (ref "IC3") (pin "11") (pinfunction "RSVD_11") (pintype "passive"))
      (node (ref "IC3") (pin "7") (pinfunction "GND_7") (pintype "power_in"))
      (node (ref "IC4") (pin "2") (pinfunction "V-_2") (pintype "bidirectional"))
      (node (ref "IC4") (pin "3") (pinfunction "IN+_3") (pintype "bidirectional"))
      (node (ref "IC6") (pin "10") (pinfunction "RSVD_10") (pintype "passive"))
      (node (ref "IC6") (pin "11") (pinfunction "RSVD_11") (pintype "passive"))
      (node (ref "IC6") (pin "7") (pinfunction "GND_7") (pintype "power_in"))
      (node (ref "J1") (pin "7") (pinfunction "7_7") (pintype "bidirectional"))
      (node (ref "J10") (pin "2") (pinfunction "2_2") (pintype "bidirectional"))
      (node (ref "J2") (pin "4") (pinfunction "4_4") (pintype "bidirectional"))
      (node (ref "J2") (pin "5") (pinfunction "5_5") (pintype "bidirectional"))
      (node (ref "J3") (pin "7") (pinfunction "7_7") (pintype "bidirectional"))
      (node (ref "J4") (pin "2") (pinfunction "2_2") (pintype "bidirectional"))
      (node (ref "J5") (pin "7") (pinfunction "7_7") (pintype "bidirectional"))
      (node (ref "J6") (pin "7") (pinfunction "7_7") (pintype "bidirectional"))
      (node (ref "J7") (pin "2") (pinfunction "2_2") (pintype "bidirectional"))
      (node (ref "J8") (pin "2") (pinfunction "2_2") (pintype "bidirectional"))
      (node (ref "J9") (pin "2") (pinfunction "2_2") (pintype "bidirectional"))
      (node (ref "R20") (pin "1") (pinfunction "1_1") (pintype "bidirectional"))
      (node (ref "R21") (pin "1") (pinfunction "1_1") (pintype "bidirectional"))
      (node (ref "R22") (pin "1") (pinfunction "1_1") (pintype "bidirectional"))
      (node (ref "R23") (pin "1") (pinfunction "1_1") (pintype "bidirectional"))
      (node (ref "R5") (pin "1") (pinfunction "1_1") (pintype "bidirectional"))
      (node (ref "U1") (pin "1") (pinfunction "GND1_1") (pintype "power_in"))
      (node (ref "U1") (pin "10") (pinfunction "4_RSVD_GND_10") (pintype "power_in"))
      (node (ref "U1") (pin "13") (pinfunction "SA0/MISO_13") (pintype "bidirectional"))
      (node (ref "U1") (pin "14") (pinfunction "GND3_14") (pintype "power_in"))
      (node (ref "U1") (pin "19") (pinfunction "GND4_19") (pintype "power_in"))
      (node (ref "U1") (pin "20") (pinfunction "5_RSVD_GND_20") (pintype "power_in"))
      (node (ref "U1") (pin "21") (pinfunction "6_RSVD_GND_21") (pintype "power_in"))
      (node (ref "U1") (pin "22") (pinfunction "7_RSVD_GND_22") (pintype "power_in"))
      (node (ref "U1") (pin "23") (pinfunction "8_RSVD_GND_23") (pintype "power_in"))
      (node (ref "U1") (pin "24") (pinfunction "9_RSVD_GND_24") (pintype "power_in"))
      (node (ref "U1") (pin "5") (pinfunction "GND2_5") (pintype "power_in"))
      (node (ref "U1") (pin "6") (pinfunction "1_RSVD_GND_6") (pintype "power_in"))
      (node (ref "U1") (pin "7") (pinfunction "2_RSVD_GND_7") (pintype "power_in"))
      (node (ref "U1") (pin "8") (pinfunction "~{I2C}/SPI_8") (pintype "bidirectional"))
      (node (ref "U1") (pin "9") (pinfunction "3_RSVD_GND_9") (pintype "power_in"))
      (node (ref "U3") (pin "4") (pinfunction "GND_4") (pintype "power_in"))
      (node (ref "U4") (pin "1") (pinfunction "GND1_1") (pintype "power_in"))
      (node (ref "U4") (pin "10") (pinfunction "4_RSVD_GND_10") (pintype "power_in"))
      (node (ref "U4") (pin "13") (pinfunction "SA0/MISO_13") (pintype "bidirectional"))
      (node (ref "U4") (pin "14") (pinfunction "GND3_14") (pintype "power_in"))
      (node (ref "U4") (pin "19") (pinfunction "GND4_19") (pintype "power_in"))
      (node (ref "U4") (pin "20") (pinfunction "5_RSVD_GND_20") (pintype "power_in"))
      (node (ref "U4") (pin "21") (pinfunction "6_RSVD_GND_21") (pintype "power_in"))
      (node (ref "U4") (pin "22") (pinfunction "7_RSVD_GND_22") (pintype "power_in"))
      (node (ref "U4") (pin "23") (pinfunction "8_RSVD_GND_23") (pintype "power_in"))
      (node (ref "U4") (pin "24") (pinfunction "9_RSVD_GND_24") (pintype "power_in"))
      (node (ref "U4") (pin "5") (pinfunction "GND2_5") (pintype "power_in"))
      (node (ref "U4") (pin "6") (pinfunction "1_RSVD_GND_6") (pintype "power_in"))
      (node (ref "U4") (pin "7") (pinfunction "2_RSVD_GND_7") (pintype "power_in"))
      (node (ref "U4") (pin "8") (pinfunction "~{I2C}/SPI_8") (pintype "bidirectional"))
      (node (ref "U4") (pin "9") (pinfunction "3_RSVD_GND_9") (pintype "power_in"))
      (node (ref "U6") (pin "1") (pinfunction "GND1_1") (pintype "power_in"))
      (node (ref "U6") (pin "10") (pinfunction "4_RSVD_GND_10") (pintype "power_in"))
      (node (ref "U6") (pin "13") (pinfunction "SA0/MISO_13") (pintype "bidirectional"))
      (node (ref "U6") (pin "14") (pinfunction "GND3_14") (pintype "power_in"))
      (node (ref "U6") (pin "19") (pinfunction "GND4_19") (pintype "power_in"))
      (node (ref "U6") (pin "20") (pinfunction "5_RSVD_GND_20") (pintype "power_in"))
      (node (ref "U6") (pin "21") (pinfunction "6_RSVD_GND_21") (pintype "power_in"))
      (node (ref "U6") (pin "22") (pinfunction "7_RSVD_GND_22") (pintype "power_in"))
      (node (ref "U6") (pin "23") (pinfunction "8_RSVD_GND_23") (pintype "power_in"))
      (node (ref "U6") (pin "24") (pinfunction "9_RSVD_GND_24") (pintype "power_in"))
      (node (ref "U6") (pin "5") (pinfunction "GND2_5") (pintype "power_in"))
      (node (ref "U6") (pin "6") (pinfunction "1_RSVD_GND_6") (pintype "power_in"))
      (node (ref "U6") (pin "7") (pinfunction "2_RSVD_GND_7") (pintype "power_in"))
      (node (ref "U6") (pin "8") (pinfunction "~{I2C}/SPI_8") (pintype "bidirectional"))
      (node (ref "U6") (pin "9") (pinfunction "3_RSVD_GND_9") (pintype "power_in"))
    )
    (net (code "18") (name "I2C1_SCL") (class "Default")
      (node (ref "H1") (pin "44") (pinfunction "44_44") (pintype "passive"))
      (node (ref "IC6") (pin "2") (pinfunction "SLC_2") (pintype "bidirectional"))
      (node (ref "R32") (pin "1") (pinfunction "1_1") (pintype "bidirectional"))
      (node (ref "U3") (pin "6") (pinfunction "SCL_6") (pintype "input"))
      (node (ref "U6") (pin "11") (pinfunction "SCL/SCLK_11") (pintype "bidirectional"))
    )
    (net (code "19") (name "I2C1_SDA") (class "Default")
      (node (ref "H1") (pin "42") (pinfunction "42_42") (pintype "passive"))
      (node (ref "IC6") (pin "3") (pinfunction "SDA_3") (pintype "bidirectional"))
      (node (ref "R31") (pin "1") (pinfunction "1_1") (pintype "bidirectional"))
      (node (ref "U3") (pin "5") (pinfunction "SDA_5") (pintype "bidirectional"))
      (node (ref "U6") (pin "12") (pinfunction "SDA/MOSI/SPI_DATA_12") (pintype "bidirectional"))
    )
    (net (code "20") (name "I2C2_SCL") (class "Default")
      (node (ref "ADC") (pin "3") (pinfunction "SCL_3") (pintype "input"))
      (node (ref "H1") (pin "37") (pinfunction "37_37") (pintype "passive"))
      (node (ref "IC2") (pin "2") (pinfunction "SLC_2") (pintype "bidirectional"))
      (node (ref "R34") (pin "1") (pinfunction "1_1") (pintype "bidirectional"))
      (node (ref "U1") (pin "11") (pinfunction "SCL/SCLK_11") (pintype "bidirectional"))
    )
    (net (code "21") (name "I2C2_SDA") (class "Default")
      (node (ref "ADC") (pin "2") (pinfunction "SDA_2") (pintype "bidirectional"))
      (node (ref "H1") (pin "35") (pinfunction "35_35") (pintype "passive"))
      (node (ref "IC2") (pin "3") (pinfunction "SDA_3") (pintype "bidirectional"))
      (node (ref "R33") (pin "1") (pinfunction "1_1") (pintype "bidirectional"))
      (node (ref "U1") (pin "12") (pinfunction "SDA/MOSI/SPI_DATA_12") (pintype "bidirectional"))
    )
    (net (code "22") (name "I2C3_SCL") (class "Default")
      (node (ref "H1") (pin "51") (pinfunction "51_51") (pintype "passive"))
      (node (ref "IC3") (pin "2") (pinfunction "SLC_2") (pintype "bidirectional"))
      (node (ref "J4") (pin "6") (pinfunction "6_6") (pintype "bidirectional"))
      (node (ref "R36") (pin "1") (pinfunction "1_1") (pintype "bidirectional"))
      (node (ref "U4") (pin "11") (pinfunction "SCL/SCLK_11") (pintype "bidirectional"))
    )
    (net (code "23") (name "I2C3_SDA") (class "Default")
      (node (ref "H1") (pin "49") (pinfunction "49_49") (pintype "passive"))
      (node (ref "IC3") (pin "3") (pinfunction "SDA_3") (pintype "bidirectional"))
      (node (ref "J4") (pin "7") (pinfunction "7_7") (pintype "bidirectional"))
      (node (ref "R35") (pin "1") (pinfunction "1_1") (pintype "bidirectional"))
      (node (ref "U4") (pin "12") (pinfunction "SDA/MOSI/SPI_DATA_12") (pintype "bidirectional"))
    )
    (net (code "24") (name "Net-(IC2-C1)") (class "Default")
      (node (ref "C7") (pin "1") (pinfunction "1_1") (pintype "bidirectional"))
      (node (ref "IC2") (pin "6") (pinfunction "C1_6") (pintype "passive"))
    )
    (net (code "25") (name "Net-(IC2-SETC)") (class "Default")
      (node (ref "C11") (pin "2") (pinfunction "2_2") (pintype "bidirectional"))
      (node (ref "IC2") (pin "13") (pinfunction "SETC_13") (pintype "passive"))
    )
    (net (code "26") (name "Net-(IC2-SETP)") (class "Default")
      (node (ref "C11") (pin "1") (pinfunction "1_1") (pintype "bidirectional"))
      (node (ref "IC2") (pin "12") (pinfunction "SETP_12") (pintype "passive"))
    )
    (net (code "27") (name "Net-(IC3-C1)") (class "Default")
      (node (ref "C6") (pin "1") (pinfunction "1_1") (pintype "bidirectional"))
      (node (ref "IC3") (pin "6") (pinfunction "C1_6") (pintype "passive"))
    )
    (net (code "28") (name "Net-(IC3-SETC)") (class "Default")
      (node (ref "C8") (pin "2") (pinfunction "2_2") (pintype "bidirectional"))
      (node (ref "IC3") (pin "13") (pinfunction "SETC_13") (pintype "passive"))
    )
    (net (code "29") (name "Net-(IC3-SETP)") (class "Default")
      (node (ref "C8") (pin "1") (pinfunction "1_1") (pintype "bidirectional"))
      (node (ref "IC3") (pin "12") (pinfunction "SETP_12") (pintype "passive"))
    )
    (net (code "30") (name "Net-(IC6-C1)") (class "Default")
      (node (ref "C33") (pin "1") (pinfunction "1_1") (pintype "bidirectional"))
      (node (ref "IC6") (pin "6") (pinfunction "C1_6") (pintype "passive"))
    )
    (net (code "31") (name "Net-(IC6-SETC)") (class "Default")
      (node (ref "C12") (pin "2") (pinfunction "2_2") (pintype "bidirectional"))
      (node (ref "IC6") (pin "13") (pinfunction "SETC_13") (pintype "passive"))
    )
    (net (code "32") (name "Net-(IC6-SETP)") (class "Default")
      (node (ref "C12") (pin "1") (pinfunction "1_1") (pintype "bidirectional"))
      (node (ref "IC6") (pin "12") (pinfunction "SETP_12") (pintype "passive"))
    )
    (net (code "33") (name "Net-(LED1-K)") (class "Default")
      (node (ref "LED1") (pin "1") (pinfunction "K_1") (pintype "bidirectional"))
      (node (ref "R5") (pin "2") (pinfunction "2_2") (pintype "bidirectional"))
    )
    (net (code "34") (name "Net-(LED5-K)") (class "Default")
      (node (ref "LED5") (pin "1") (pinfunction "K_1") (pintype "bidirectional"))
      (node (ref "R21") (pin "2") (pinfunction "2_2") (pintype "bidirectional"))
    )
    (net (code "35") (name "Net-(LED6-K)") (class "Default")
      (node (ref "LED6") (pin "1") (pinfunction "K_1") (pintype "bidirectional"))
      (node (ref "R22") (pin "2") (pinfunction "2_2") (pintype "bidirectional"))
    )
    (net (code "36") (name "Net-(LED8-K)") (class "Default")
      (node (ref "LED8") (pin "1") (pinfunction "K_1") (pintype "bidirectional"))
      (node (ref "R23") (pin "2") (pinfunction "2_2") (pintype "bidirectional"))
    )
    (net (code "37") (name "Net-(U1-VREGD)") (class "Default")
      (node (ref "C1") (pin "1") (pinfunction "1_1") (pintype "bidirectional"))
      (node (ref "U1") (pin "16") (pinfunction "VREGD_16") (pintype "output"))
    )
    (net (code "38") (name "Net-(U3-VBAT)") (class "Default")
      (node (ref "BT1") (pin "+") (pinfunction "+_+") (pintype "passive"))
      (node (ref "U3") (pin "3") (pinfunction "VBAT_3") (pintype "power_in"))
    )
    (net (code "39") (name "Net-(U3-X1)") (class "Default")
      (node (ref "U3") (pin "1") (pinfunction "X1_1") (pintype "input"))
      (node (ref "Y1") (pin "1") (pinfunction "1_1") (pintype "passive"))
    )
    (net (code "40") (name "Net-(U3-X2)") (class "Default")
      (node (ref "U3") (pin "2") (pinfunction "X2_2") (pintype "output"))
      (node (ref "Y1") (pin "2") (pinfunction "2_2") (pintype "passive"))
    )
    (net (code "41") (name "Net-(U4-VREGD)") (class "Default")
      (node (ref "C10") (pin "1") (pinfunction "1_1") (pintype "bidirectional"))
      (node (ref "U4") (pin "16") (pinfunction "VREGD_16") (pintype "output"))
    )
    (net (code "42") (name "Net-(U6-VREGD)") (class "Default")
      (node (ref "C16") (pin "1") (pinfunction "1_1") (pintype "bidirectional"))
      (node (ref "U6") (pin "16") (pinfunction "VREGD_16") (pintype "output"))
    )
    (net (code "43") (name "PH1_POS") (class "Default")
      (node (ref "IC1") (pin "2") (pinfunction "IN1-_2") (pintype "bidirectional"))
      (node (ref "J8") (pin "1") (pinfunction "1_1") (pintype "bidirectional"))
      (node (ref "R12") (pin "2") (pinfunction "2_2") (pintype "bidirectional"))
    )
    (net (code "44") (name "PH2_POS") (class "Default")
      (node (ref "IC1") (pin "6") (pinfunction "IN2-_6") (pintype "bidirectional"))
      (node (ref "J10") (pin "1") (pinfunction "1_1") (pintype "bidirectional"))
      (node (ref "R14") (pin "2") (pinfunction "2_2") (pintype "bidirectional"))
    )
    (net (code "45") (name "PH3_POS") (class "Default")
      (node (ref "IC1") (pin "9") (pinfunction "IN3-_9") (pintype "bidirectional"))
      (node (ref "J7") (pin "1") (pinfunction "1_1") (pintype "bidirectional"))
      (node (ref "R15") (pin "2") (pinfunction "2_2") (pintype "bidirectional"))
    )
    (net (code "46") (name "PH4_POS") (class "Default")
      (node (ref "IC1") (pin "13") (pinfunction "IN4-_13") (pintype "bidirectional"))
      (node (ref "J9") (pin "1") (pinfunction "1_1") (pintype "bidirectional"))
      (node (ref "R19") (pin "2") (pinfunction "2_2") (pintype "bidirectional"))
    )
    (net (code "47") (name "PH5_POS") (class "Default")
      (node (ref "H1") (pin "36") (pinfunction "36_36") (pintype "passive"))
      (node (ref "IC4") (pin "4") (pinfunction "IN-_4") (pintype "bidirectional"))
      (node (ref "R10") (pin "2") (pinfunction "2_2") (pintype "bidirectional"))
    )
    (net (code "48") (name "SPI_EN_1") (class "Default")
      (node (ref "H1") (pin "7") (pinfunction "7_7") (pintype "passive"))
      (node (ref "J1") (pin "2") (pinfunction "2_2") (pintype "bidirectional"))
    )
    (net (code "49") (name "SPI_EN_2") (class "Default")
      (node (ref "H1") (pin "8") (pinfunction "8_8") (pintype "passive"))
      (node (ref "J3") (pin "2") (pinfunction "2_2") (pintype "bidirectional"))
    )
    (net (code "50") (name "SPI_EN_3") (class "Default")
      (node (ref "H1") (pin "22") (pinfunction "22_22") (pintype "passive"))
      (node (ref "J5") (pin "2") (pinfunction "2_2") (pintype "bidirectional"))
    )
    (net (code "51") (name "SPI_EN_4") (class "Default")
      (node (ref "H1") (pin "21") (pinfunction "21_21") (pintype "passive"))
      (node (ref "J6") (pin "2") (pinfunction "2_2") (pintype "bidirectional"))
    )
    (net (code "52") (name "SPI_MISO") (class "Default")
      (node (ref "H1") (pin "18") (pinfunction "18_18") (pintype "passive"))
      (node (ref "J1") (pin "4") (pinfunction "4_4") (pintype "bidirectional"))
      (node (ref "J3") (pin "4") (pinfunction "4_4") (pintype "bidirectional"))
      (node (ref "J5") (pin "4") (pinfunction "4_4") (pintype "bidirectional"))
      (node (ref "J6") (pin "4") (pinfunction "4_4") (pintype "bidirectional"))
    )
    (net (code "53") (name "SPI_MOSI") (class "Default")
      (node (ref "H1") (pin "16") (pinfunction "16_16") (pintype "passive"))
      (node (ref "J1") (pin "3") (pinfunction "3_3") (pintype "bidirectional"))
      (node (ref "J3") (pin "3") (pinfunction "3_3") (pintype "bidirectional"))
      (node (ref "J5") (pin "3") (pinfunction "3_3") (pintype "bidirectional"))
      (node (ref "J6") (pin "3") (pinfunction "3_3") (pintype "bidirectional"))
    )
    (net (code "54") (name "SPI_SCK") (class "Default")
      (node (ref "H1") (pin "12") (pinfunction "12_12") (pintype "passive"))
      (node (ref "J1") (pin "5") (pinfunction "5_5") (pintype "bidirectional"))
      (node (ref "J3") (pin "5") (pinfunction "5_5") (pintype "bidirectional"))
      (node (ref "J5") (pin "5") (pinfunction "5_5") (pintype "bidirectional"))
      (node (ref "J6") (pin "5") (pinfunction "5_5") (pintype "bidirectional"))
    )
    (net (code "55") (name "SPI_SS_1") (class "Default")
      (node (ref "H1") (pin "9") (pinfunction "9_9") (pintype "passive"))
      (node (ref "J1") (pin "6") (pinfunction "6_6") (pintype "bidirectional"))
    )
    (net (code "56") (name "SPI_SS_2") (class "Default")
      (node (ref "H1") (pin "10") (pinfunction "10_10") (pintype "passive"))
      (node (ref "J3") (pin "6") (pinfunction "6_6") (pintype "bidirectional"))
    )
    (net (code "57") (name "SPI_SS_3") (class "Default")
      (node (ref "H1") (pin "20") (pinfunction "20_20") (pintype "passive"))
      (node (ref "J5") (pin "6") (pinfunction "6_6") (pintype "bidirectional"))
    )
    (net (code "58") (name "SPI_SS_4") (class "Default")
      (node (ref "H1") (pin "19") (pinfunction "19_19") (pintype "passive"))
      (node (ref "J6") (pin "6") (pinfunction "6_6") (pintype "bidirectional"))
    )
    (net (code "59") (name "UART2_RX") (class "Default")
      (node (ref "H1") (pin "4") (pinfunction "4_4") (pintype "passive"))
    )
    (net (code "60") (name "UART2_TX") (class "Default")
      (node (ref "H1") (pin "2") (pinfunction "2_2") (pintype "passive"))
    )
    (net (code "61") (name "UART3_RX") (class "Default")
      (node (ref "H1") (pin "52") (pinfunction "52_52") (pintype "passive"))
      (node (ref "J2") (pin "7") (pinfunction "7_7") (pintype "bidirectional"))
    )
    (net (code "62") (name "UART3_TX") (class "Default")
      (node (ref "H1") (pin "50") (pinfunction "50_50") (pintype "passive"))
      (node (ref "J2") (pin "8") (pinfunction "8_8") (pintype "bidirectional"))
    )
    (net (code "63") (name "UART8_RX") (class "Default")
      (node (ref "H1") (pin "3") (pinfunction "3_3") (pintype "passive"))
      (node (ref "J4") (pin "4") (pinfunction "4_4") (pintype "bidirectional"))
    )
    (net (code "64") (name "UART8_TX") (class "Default")
      (node (ref "H1") (pin "1") (pinfunction "1_1") (pintype "passive"))
      (node (ref "J4") (pin "3") (pinfunction "3_3") (pintype "bidirectional"))
    )
    (net (code "65") (name "unconnected-(ADC-A0-Pad7)") (class "Default")
      (node (ref "ADC") (pin "7") (pinfunction "A0_7") (pintype "input"))
    )
    (net (code "66") (name "unconnected-(ADC-A1-Pad8)") (class "Default")
      (node (ref "ADC") (pin "8") (pinfunction "A1_8") (pintype "input"))
    )
    (net (code "67") (name "unconnected-(ADC-IN5-Pad11)") (class "Default")
      (node (ref "ADC") (pin "11") (pinfunction "IN5_11") (pintype "input"))
    )
    (net (code "68") (name "unconnected-(ADC-IN6-Pad10)") (class "Default")
      (node (ref "ADC") (pin "10") (pinfunction "IN6_10") (pintype "input"))
    )
    (net (code "69") (name "unconnected-(ADC-IN7-Pad9)") (class "Default")
      (node (ref "ADC") (pin "9") (pinfunction "IN7_9") (pintype "input"))
    )
    (net (code "70") (name "unconnected-(ADC-INT-Pad6)") (class "Default")
      (node (ref "ADC") (pin "6") (pinfunction "INT_6") (pintype "output"))
    )
    (net (code "71") (name "unconnected-(H1-Pad6)") (class "Default")
      (node (ref "H1") (pin "6") (pinfunction "6_6") (pintype "passive"))
    )
    (net (code "72") (name "unconnected-(H1-Pad11)") (class "Default")
      (node (ref "H1") (pin "11") (pinfunction "11_11") (pintype "passive"))
    )
    (net (code "73") (name "unconnected-(H1-Pad13)") (class "Default")
      (node (ref "H1") (pin "13") (pinfunction "13_13") (pintype "passive"))
    )
    (net (code "74") (name "unconnected-(H1-Pad14)") (class "Default")
      (node (ref "H1") (pin "14") (pinfunction "14_14") (pintype "passive"))
    )
    (net (code "75") (name "unconnected-(H1-Pad15)") (class "Default")
      (node (ref "H1") (pin "15") (pinfunction "15_15") (pintype "passive"))
    )
    (net (code "76") (name "unconnected-(H1-Pad17)") (class "Default")
      (node (ref "H1") (pin "17") (pinfunction "17_17") (pintype "passive"))
    )
    (net (code "77") (name "unconnected-(H1-Pad23)") (class "Default")
      (node (ref "H1") (pin "23") (pinfunction "23_23") (pintype "passive"))
    )
    (net (code "78") (name "unconnected-(H1-Pad24)") (class "Default")
      (node (ref "H1") (pin "24") (pinfunction "24_24") (pintype "passive"))
    )
    (net (code "79") (name "unconnected-(H1-Pad25)") (class "Default")
      (node (ref "H1") (pin "25") (pinfunction "25_25") (pintype "passive"))
    )
    (net (code "80") (name "unconnected-(H1-Pad26)") (class "Default")
      (node (ref "H1") (pin "26") (pinfunction "26_26") (pintype "passive"))
    )
    (net (code "81") (name "unconnected-(H1-Pad27)") (class "Default")
      (node (ref "H1") (pin "27") (pinfunction "27_27") (pintype "passive"))
    )
    (net (code "82") (name "unconnected-(H1-Pad28)") (class "Default")
      (node (ref "H1") (pin "28") (pinfunction "28_28") (pintype "passive"))
    )
    (net (code "83") (name "unconnected-(H1-Pad29)") (class "Default")
      (node (ref "H1") (pin "29") (pinfunction "29_29") (pintype "passive"))
    )
    (net (code "84") (name "unconnected-(H1-Pad30)") (class "Default")
      (node (ref "H1") (pin "30") (pinfunction "30_30") (pintype "passive"))
    )
    (net (code "85") (name "unconnected-(H1-Pad31)") (class "Default")
      (node (ref "H1") (pin "31") (pinfunction "31_31") (pintype "passive"))
    )
    (net (code "86") (name "unconnected-(H1-Pad32)") (class "Default")
      (node (ref "H1") (pin "32") (pinfunction "32_32") (pintype "passive"))
    )
    (net (code "87") (name "unconnected-(H1-Pad33)") (class "Default")
      (node (ref "H1") (pin "33") (pinfunction "33_33") (pintype "passive"))
    )
    (net (code "88") (name "unconnected-(H1-Pad34)") (class "Default")
      (node (ref "H1") (pin "34") (pinfunction "34_34") (pintype "passive"))
    )
    (net (code "89") (name "unconnected-(H1-Pad39)") (class "Default")
      (node (ref "H1") (pin "39") (pinfunction "39_39") (pintype "passive"))
    )
    (net (code "90") (name "unconnected-(H1-Pad40)") (class "Default")
      (node (ref "H1") (pin "40") (pinfunction "40_40") (pintype "passive"))
    )
    (net (code "91") (name "unconnected-(H1-Pad41)") (class "Default")
      (node (ref "H1") (pin "41") (pinfunction "41_41") (pintype "passive"))
    )
    (net (code "92") (name "unconnected-(H1-Pad43)") (class "Default")
      (node (ref "H1") (pin "43") (pinfunction "43_43") (pintype "passive"))
    )
    (net (code "93") (name "unconnected-(H1-Pad45)") (class "Default")
      (node (ref "H1") (pin "45") (pinfunction "45_45") (pintype "passive"))
    )
    (net (code "94") (name "unconnected-(H1-Pad46)") (class "Default")
      (node (ref "H1") (pin "46") (pinfunction "46_46") (pintype "passive"))
    )
    (net (code "95") (name "unconnected-(H1-Pad47)") (class "Default")
      (node (ref "H1") (pin "47") (pinfunction "47_47") (pintype "passive"))
    )
    (net (code "96") (name "unconnected-(H1-Pad48)") (class "Default")
      (node (ref "H1") (pin "48") (pinfunction "48_48") (pintype "passive"))
    )
    (net (code "97") (name "unconnected-(H2-Pad1)") (class "Default")
      (node (ref "H2") (pin "1") (pinfunction "1_1") (pintype "passive"))
    )
    (net (code "98") (name "unconnected-(H2-Pad2)") (class "Default")
      (node (ref "H2") (pin "2") (pinfunction "2_2") (pintype "passive"))
    )
    (net (code "99") (name "unconnected-(H2-Pad3)") (class "Default")
      (node (ref "H2") (pin "3") (pinfunction "3_3") (pintype "passive"))
    )
    (net (code "100") (name "unconnected-(H2-Pad4)") (class "Default")
      (node (ref "H2") (pin "4") (pinfunction "4_4") (pintype "passive"))
    )
    (net (code "101") (name "unconnected-(H2-Pad5)") (class "Default")
      (node (ref "H2") (pin "5") (pinfunction "5_5") (pintype "passive"))
    )
    (net (code "102") (name "unconnected-(H2-Pad6)") (class "Default")
      (node (ref "H2") (pin "6") (pinfunction "6_6") (pintype "passive"))
    )
    (net (code "103") (name "unconnected-(H2-Pad7)") (class "Default")
      (node (ref "H2") (pin "7") (pinfunction "7_7") (pintype "passive"))
    )
    (net (code "104") (name "unconnected-(H2-Pad8)") (class "Default")
      (node (ref "H2") (pin "8") (pinfunction "8_8") (pintype "passive"))
    )
    (net (code "105") (name "unconnected-(H2-Pad9)") (class "Default")
      (node (ref "H2") (pin "9") (pinfunction "9_9") (pintype "passive"))
    )
    (net (code "106") (name "unconnected-(H2-Pad11)") (class "Default")
      (node (ref "H2") (pin "11") (pinfunction "11_11") (pintype "passive"))
    )
    (net (code "107") (name "unconnected-(H2-Pad12)") (class "Default")
      (node (ref "H2") (pin "12") (pinfunction "12_12") (pintype "passive"))
    )
    (net (code "108") (name "unconnected-(H2-Pad23)") (class "Default")
      (node (ref "H2") (pin "23") (pinfunction "23_23") (pintype "passive"))
    )
    (net (code "109") (name "unconnected-(H2-Pad24)") (class "Default")
      (node (ref "H2") (pin "24") (pinfunction "24_24") (pintype "passive"))
    )
    (net (code "110") (name "unconnected-(H2-Pad32)") (class "Default")
      (node (ref "H2") (pin "32") (pinfunction "32_32") (pintype "passive"))
    )
    (net (code "111") (name "unconnected-(H2-Pad33)") (class "Default")
      (node (ref "H2") (pin "33") (pinfunction "33_33") (pintype "passive"))
    )
    (net (code "112") (name "unconnected-(H2-Pad34)") (class "Default")
      (node (ref "H2") (pin "34") (pinfunction "34_34") (pintype "passive"))
    )
    (net (code "113") (name "unconnected-(H2-Pad35)") (class "Default")
      (node (ref "H2") (pin "35") (pinfunction "35_35") (pintype "passive"))
    )
    (net (code "114") (name "unconnected-(H2-Pad36)") (class "Default")
      (node (ref "H2") (pin "36") (pinfunction "36_36") (pintype "passive"))
    )
    (net (code "115") (name "unconnected-(H2-Pad37)") (class "Default")
      (node (ref "H2") (pin "37") (pinfunction "37_37") (pintype "passive"))
    )
    (net (code "116") (name "unconnected-(H2-Pad38)") (class "Default")
      (node (ref "H2") (pin "38") (pinfunction "38_38") (pintype "passive"))
    )
    (net (code "117") (name "unconnected-(H2-Pad39)") (class "Default")
      (node (ref "H2") (pin "39") (pinfunction "39_39") (pintype "passive"))
    )
    (net (code "118") (name "unconnected-(H2-Pad40)") (class "Default")
      (node (ref "H2") (pin "40") (pinfunction "40_40") (pintype "passive"))
    )
    (net (code "119") (name "unconnected-(H2-Pad41)") (class "Default")
      (node (ref "H2") (pin "41") (pinfunction "41_41") (pintype "passive"))
    )
    (net (code "120") (name "unconnected-(H2-Pad42)") (class "Default")
      (node (ref "H2") (pin "42") (pinfunction "42_42") (pintype "passive"))
    )
    (net (code "121") (name "unconnected-(H2-Pad43)") (class "Default")
      (node (ref "H2") (pin "43") (pinfunction "43_43") (pintype "passive"))
    )
    (net (code "122") (name "unconnected-(H2-Pad44)") (class "Default")
      (node (ref "H2") (pin "44") (pinfunction "44_44") (pintype "passive"))
    )
    (net (code "123") (name "unconnected-(H2-Pad45)") (class "Default")
      (node (ref "H2") (pin "45") (pinfunction "45_45") (pintype "passive"))
    )
    (net (code "124") (name "unconnected-(H2-Pad46)") (class "Default")
      (node (ref "H2") (pin "46") (pinfunction "46_46") (pintype "passive"))
    )
    (net (code "125") (name "unconnected-(H2-Pad50)") (class "Default")
      (node (ref "H2") (pin "50") (pinfunction "50_50") (pintype "passive"))
    )
    (net (code "126") (name "unconnected-(H2-Pad51)") (class "Default")
      (node (ref "H2") (pin "51") (pinfunction "51_51") (pintype "passive"))
    )
    (net (code "127") (name "unconnected-(H2-Pad52)") (class "Default")
      (node (ref "H2") (pin "52") (pinfunction "52_52") (pintype "passive"))
    )
    (net (code "128") (name "unconnected-(IC2-DRDY-Pad9)") (class "Default")
      (node (ref "IC2") (pin "9") (pinfunction "DRDY_9") (pintype "bidirectional"))
    )
    (net (code "129") (name "unconnected-(IC2-INT1-Pad5)") (class "Default")
      (node (ref "IC2") (pin "5") (pinfunction "INT1_5") (pintype "bidirectional"))
    )
    (net (code "130") (name "unconnected-(IC2-INT2-Pad4)") (class "Default")
      (node (ref "IC2") (pin "4") (pinfunction "INT2_4") (pintype "bidirectional"))
    )
    (net (code "131") (name "unconnected-(IC3-DRDY-Pad9)") (class "Default")
      (node (ref "IC3") (pin "9") (pinfunction "DRDY_9") (pintype "bidirectional"))
    )
    (net (code "132") (name "unconnected-(IC3-INT1-Pad5)") (class "Default")
      (node (ref "IC3") (pin "5") (pinfunction "INT1_5") (pintype "bidirectional"))
    )
    (net (code "133") (name "unconnected-(IC3-INT2-Pad4)") (class "Default")
      (node (ref "IC3") (pin "4") (pinfunction "INT2_4") (pintype "bidirectional"))
    )
    (net (code "134") (name "unconnected-(IC6-DRDY-Pad9)") (class "Default")
      (node (ref "IC6") (pin "9") (pinfunction "DRDY_9") (pintype "bidirectional"))
    )
    (net (code "135") (name "unconnected-(IC6-INT1-Pad5)") (class "Default")
      (node (ref "IC6") (pin "5") (pinfunction "INT1_5") (pintype "bidirectional"))
    )
    (net (code "136") (name "unconnected-(IC6-INT2-Pad4)") (class "Default")
      (node (ref "IC6") (pin "4") (pinfunction "INT2_4") (pintype "bidirectional"))
    )
    (net (code "137") (name "unconnected-(J2-Pad6)") (class "Default")
      (node (ref "J2") (pin "6") (pinfunction "6_6") (pintype "bidirectional"))
    )
    (net (code "138") (name "unconnected-(J2-Pad9)") (class "Default")
      (node (ref "J2") (pin "9") (pinfunction "9_9") (pintype "bidirectional"))
    )
    (net (code "139") (name "unconnected-(J2-Pad10)") (class "Default")
      (node (ref "J2") (pin "10") (pinfunction "10_10") (pintype "bidirectional"))
    )
    (net (code "140") (name "unconnected-(J2-PadMP1)") (class "Default")
      (node (ref "J2") (pin "MP1") (pinfunction "MP1_MP1") (pintype "bidirectional"))
    )
    (net (code "141") (name "unconnected-(J2-PadMP2)") (class "Default")
      (node (ref "J2") (pin "MP2") (pinfunction "MP2_MP2") (pintype "bidirectional"))
    )
    (net (code "142") (name "unconnected-(J4-Pad9)") (class "Default")
      (node (ref "J4") (pin "9") (pinfunction "9_9") (pintype "bidirectional"))
    )
    (net (code "143") (name "unconnected-(J4-Pad10)") (class "Default")
      (node (ref "J4") (pin "10") (pinfunction "10_10") (pintype "bidirectional"))
    )
    (net (code "144") (name "unconnected-(J7-PadMP1)") (class "Default")
      (node (ref "J7") (pin "MP1") (pinfunction "MP1_MP1") (pintype "bidirectional"))
    )
    (net (code "145") (name "unconnected-(J7-PadMP2)") (class "Default")
      (node (ref "J7") (pin "MP2") (pinfunction "MP2_MP2") (pintype "bidirectional"))
    )
    (net (code "146") (name "unconnected-(J8-PadMP1)") (class "Default")
      (node (ref "J8") (pin "MP1") (pinfunction "MP1_MP1") (pintype "bidirectional"))
    )
    (net (code "147") (name "unconnected-(J8-PadMP2)") (class "Default")
      (node (ref "J8") (pin "MP2") (pinfunction "MP2_MP2") (pintype "bidirectional"))
    )
    (net (code "148") (name "unconnected-(J9-PadMP1)") (class "Default")
      (node (ref "J9") (pin "MP1") (pinfunction "MP1_MP1") (pintype "bidirectional"))
    )
    (net (code "149") (name "unconnected-(J9-PadMP2)") (class "Default")
      (node (ref "J9") (pin "MP2") (pinfunction "MP2_MP2") (pintype "bidirectional"))
    )
    (net (code "150") (name "unconnected-(J10-PadMP1)") (class "Default")
      (node (ref "J10") (pin "MP1") (pinfunction "MP1_MP1") (pintype "bidirectional"))
    )
    (net (code "151") (name "unconnected-(J10-PadMP2)") (class "Default")
      (node (ref "J10") (pin "MP2") (pinfunction "MP2_MP2") (pintype "bidirectional"))
    )
    (net (code "152") (name "unconnected-(U1-INT1-Pad3)") (class "Default")
      (node (ref "U1") (pin "3") (pinfunction "INT1_3") (pintype "output"))
    )
    (net (code "153") (name "unconnected-(U1-INT2{slash}PWR_CTRL-Pad2)") (class "Default")
      (node (ref "U1") (pin "2") (pinfunction "INT2/PWR_CTRL_2") (pintype "bidirectional"))
    )
    (net (code "154") (name "unconnected-(U3-SQW-Pad7)") (class "Default")
      (node (ref "U3") (pin "7") (pinfunction "SQW_7") (pintype "output"))
    )
    (net (code "155") (name "unconnected-(U4-INT1-Pad3)") (class "Default")
      (node (ref "U4") (pin "3") (pinfunction "INT1_3") (pintype "output"))
    )
    (net (code "156") (name "unconnected-(U4-INT2{slash}PWR_CTRL-Pad2)") (class "Default")
      (node (ref "U4") (pin "2") (pinfunction "INT2/PWR_CTRL_2") (pintype "bidirectional"))
    )
    (net (code "157") (name "unconnected-(U6-INT1-Pad3)") (class "Default")
      (node (ref "U6") (pin "3") (pinfunction "INT1_3") (pintype "output"))
    )
    (net (code "158") (name "unconnected-(U6-INT2{slash}PWR_CTRL-Pad2)") (class "Default")
      (node (ref "U6") (pin "2") (pinfunction "INT2/PWR_CTRL_2") (pintype "bidirectional"))
    )
  )
)
